# design.net
KiCad netlist of a schematic drawn in Altium Designer
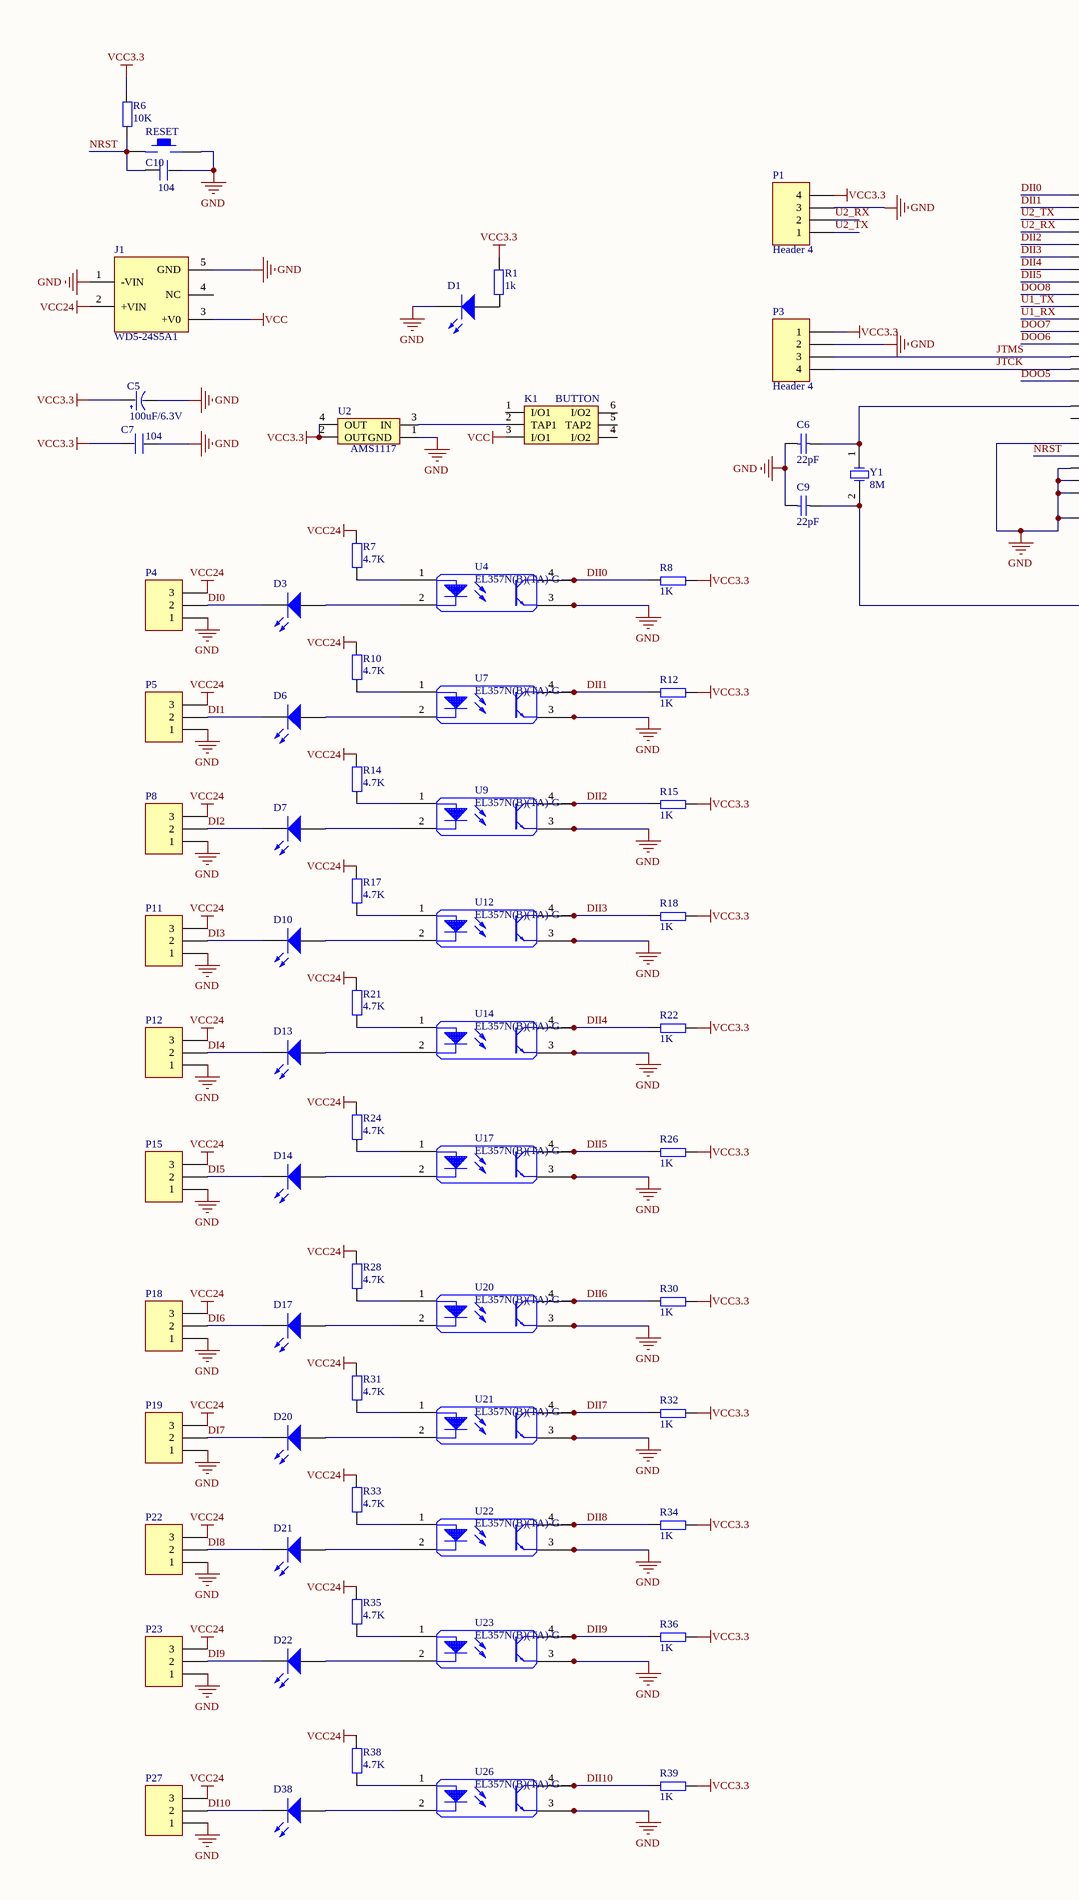
[diagram p0: 继电器板.SchDoc, left]
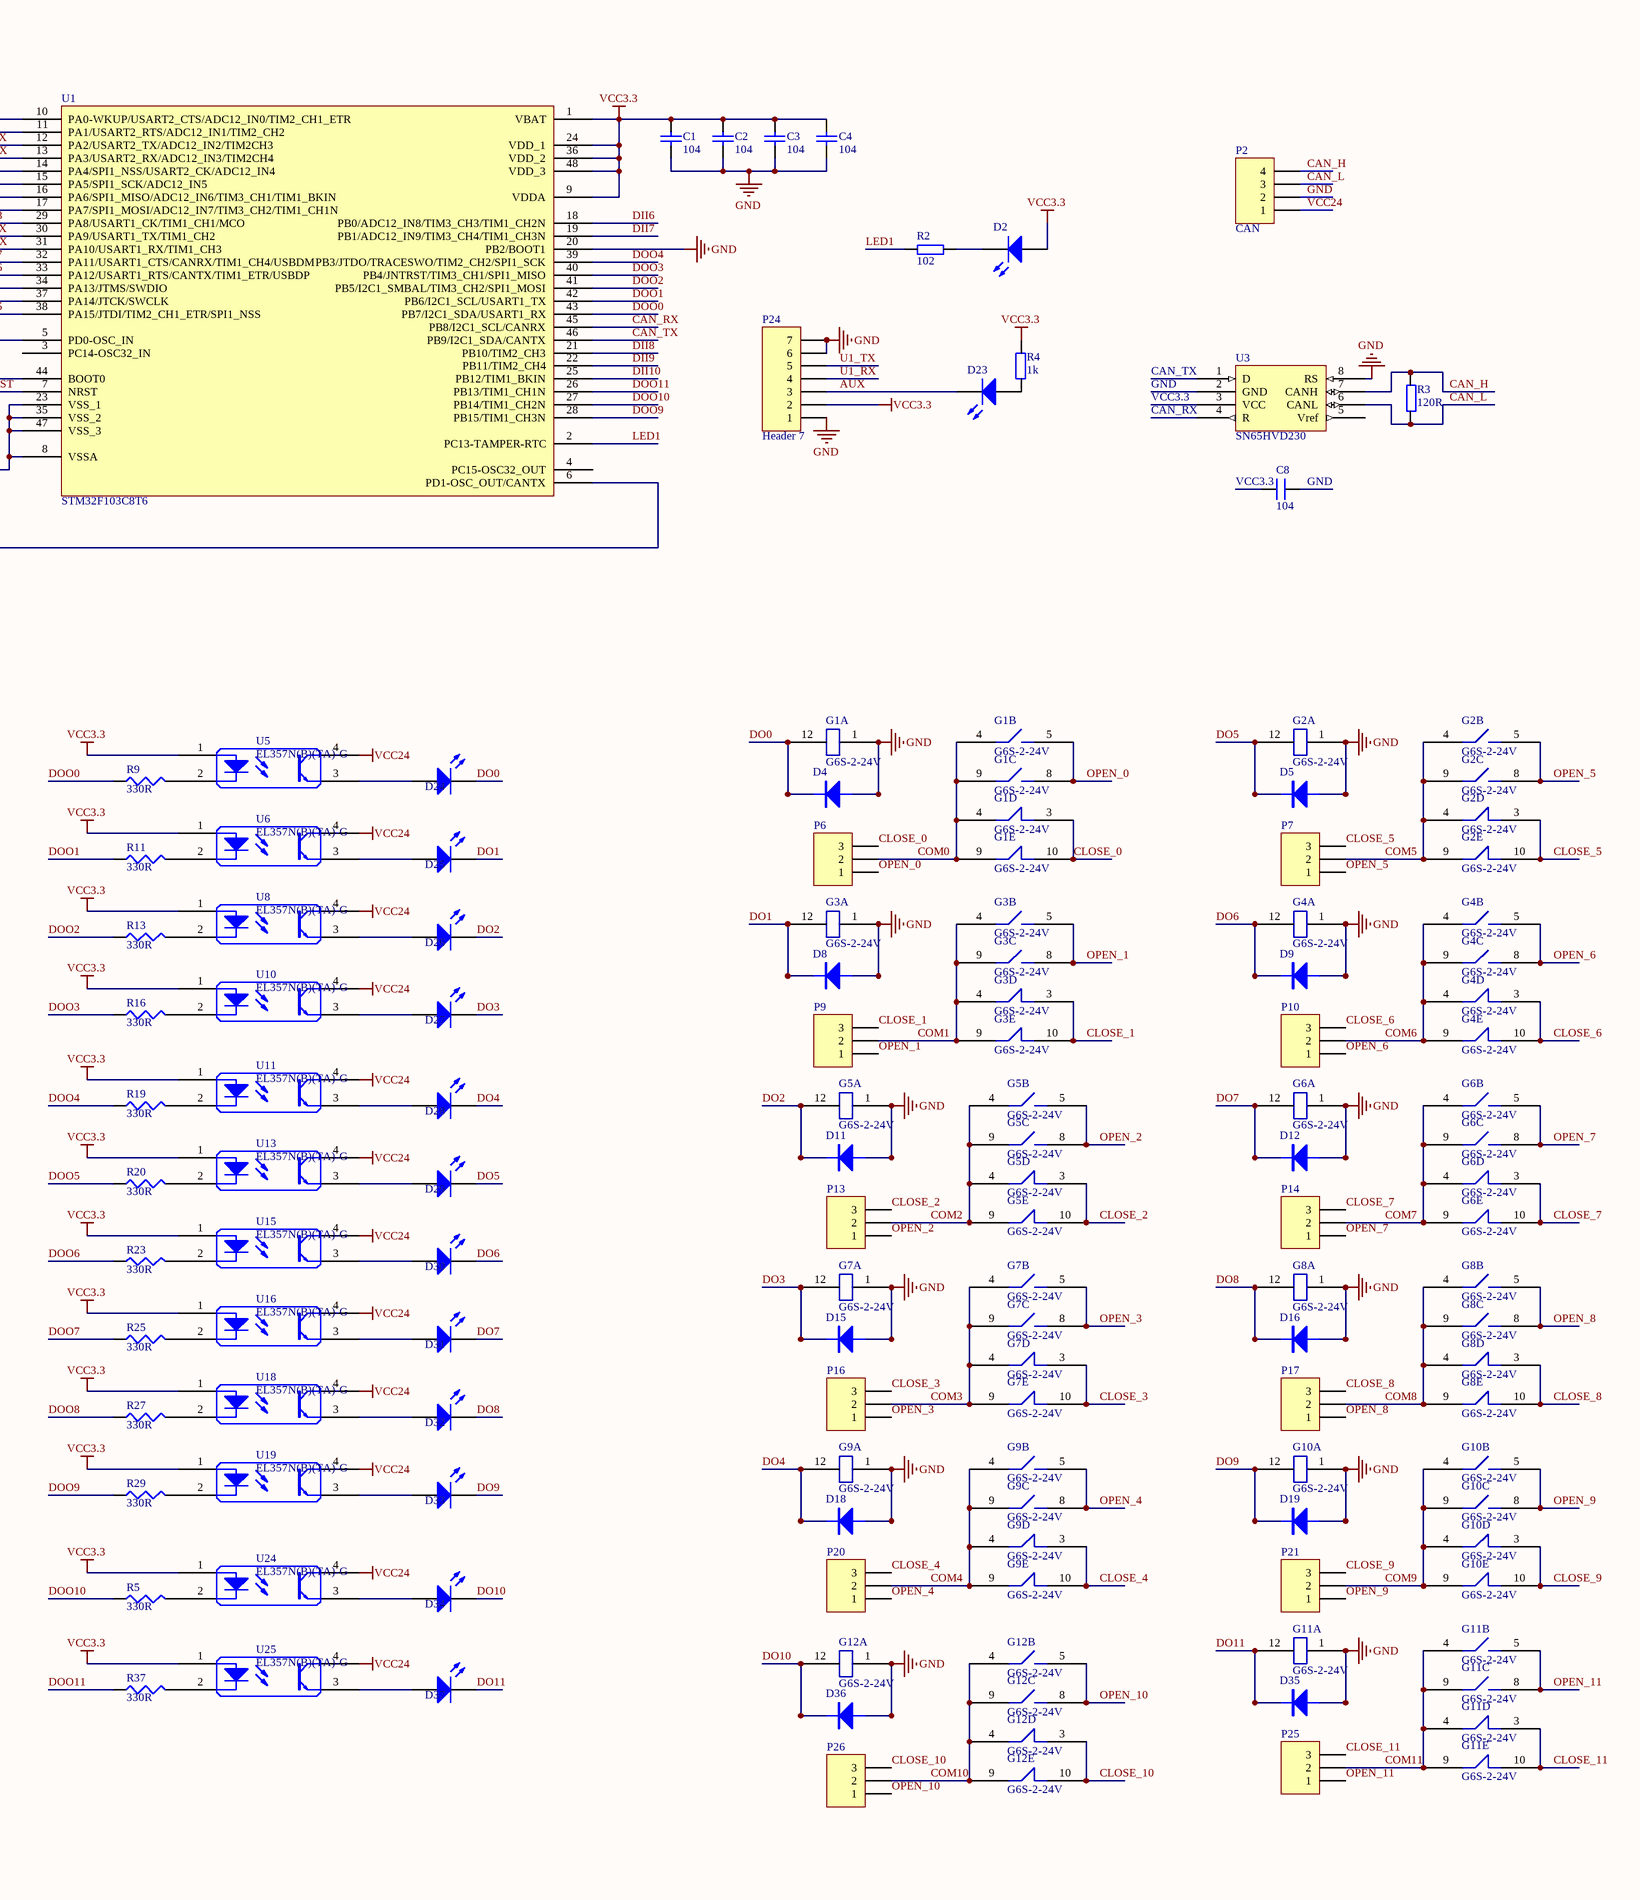
[diagram p1: 继电器板.SchDoc, right]

(export (version "E")
  (design (tool "Eeschema 10.0.6"))
  (components
    (comp (ref "C1")
      (value "104")
      (footprint "C0805")
      (description "Capacitor")
      (fields (field (name "PUBLISHER") "Altium Limited"))
      (libsource (lib "Miscellaneous Devices") (part "Cap"))
    )
    (comp (ref "C2")
      (value "104")
      (footprint "C0805")
      (description "Capacitor")
      (fields (field (name "PUBLISHER") "Altium Limited"))
      (libsource (lib "Miscellaneous Devices") (part "Cap"))
    )
    (comp (ref "C3")
      (value "104")
      (footprint "C0805")
      (description "Capacitor")
      (fields (field (name "PUBLISHER") "Altium Limited"))
      (libsource (lib "Miscellaneous Devices") (part "Cap"))
    )
    (comp (ref "C4")
      (value "104")
      (footprint "C0805")
      (description "Capacitor")
      (fields (field (name "PUBLISHER") "Altium Limited"))
      (libsource (lib "Miscellaneous Devices") (part "Cap"))
    )
    (comp (ref "C5") (value "100uF/6.3V") (footprint "3216") (libsource (lib "WarShip V3_SCH") (part "CAP")))
    (comp (ref "C6")
      (value "22pF")
      (footprint "C0805")
      (description "Capacitor")
      (fields (field (name "PUBLISHER") "Altium Limited"))
      (libsource (lib "Miscellaneous Devices") (part "Cap"))
    )
    (comp (ref "C7") (value "104") (footprint "C0805") (libsource (lib "WarShip V3_SCH") (part "C")))
    (comp (ref "C8") (value "104") (footprint "C0805") (libsource (lib "Explorer STM32F407封装库") (part "C_3")))
    (comp (ref "C9")
      (value "22pF")
      (footprint "C0805")
      (description "Capacitor")
      (fields (field (name "PUBLISHER") "Altium Limited"))
      (libsource (lib "Miscellaneous Devices") (part "Cap"))
    )
    (comp (ref "C10") (value "104") (footprint "C0805") (libsource (lib "Explorer STM32F407封装库") (part "C")))
    (comp (ref "D1")
      (value "LED0")
      (footprint "LC-0805_LED_S1")
      (description "Typical INFRARED GaAs LED")
      (fields (field (name "PUBLISHER") "Altium Limited"))
      (libsource (lib "继电器板_1") (part "LED0"))
    )
    (comp (ref "D2")
      (value "LED0")
      (footprint "LC-0805_LED_S1")
      (description "Typical INFRARED GaAs LED")
      (fields (field (name "PUBLISHER") "Altium Limited"))
      (libsource (lib "继电器板_1") (part "LED0"))
    )
    (comp (ref "D3")
      (value "LED0")
      (footprint "LC-0805_LED_S1")
      (description "Typical INFRARED GaAs LED")
      (fields (field (name "PUBLISHER") "Altium Limited"))
      (libsource (lib "继电器板_1") (part "LED0"))
    )
    (comp (ref "D4")
      (value "~")
      (footprint "LC-LL-34")
      (description "Diode")
      (libsource (lib "*") (part "DIODE"))
    )
    (comp (ref "D5")
      (value "~")
      (footprint "LC-LL-34")
      (description "Diode")
      (libsource (lib "*") (part "DIODE"))
    )
    (comp (ref "D6")
      (value "LED0")
      (footprint "LC-0805_LED_S1")
      (description "Typical INFRARED GaAs LED")
      (fields (field (name "PUBLISHER") "Altium Limited"))
      (libsource (lib "继电器板_1") (part "LED0"))
    )
    (comp (ref "D7")
      (value "LED0")
      (footprint "LC-0805_LED_S1")
      (description "Typical INFRARED GaAs LED")
      (fields (field (name "PUBLISHER") "Altium Limited"))
      (libsource (lib "继电器板_1") (part "LED0"))
    )
    (comp (ref "D8")
      (value "~")
      (footprint "LC-LL-34")
      (description "Diode")
      (libsource (lib "*") (part "DIODE"))
    )
    (comp (ref "D9")
      (value "~")
      (footprint "LC-LL-34")
      (description "Diode")
      (libsource (lib "*") (part "DIODE"))
    )
    (comp (ref "D10")
      (value "LED0")
      (footprint "LC-0805_LED_S1")
      (description "Typical INFRARED GaAs LED")
      (fields (field (name "PUBLISHER") "Altium Limited"))
      (libsource (lib "继电器板_1") (part "LED0"))
    )
    (comp (ref "D11")
      (value "~")
      (footprint "LC-LL-34")
      (description "Diode")
      (libsource (lib "*") (part "DIODE"))
    )
    (comp (ref "D12")
      (value "~")
      (footprint "LC-LL-34")
      (description "Diode")
      (libsource (lib "*") (part "DIODE"))
    )
    (comp (ref "D13")
      (value "LED0")
      (footprint "LC-0805_LED_S1")
      (description "Typical INFRARED GaAs LED")
      (fields (field (name "PUBLISHER") "Altium Limited"))
      (libsource (lib "继电器板_1") (part "LED0"))
    )
    (comp (ref "D14")
      (value "LED0")
      (footprint "LC-0805_LED_S1")
      (description "Typical INFRARED GaAs LED")
      (fields (field (name "PUBLISHER") "Altium Limited"))
      (libsource (lib "继电器板_1") (part "LED0"))
    )
    (comp (ref "D15")
      (value "~")
      (footprint "LC-LL-34")
      (description "Diode")
      (libsource (lib "*") (part "DIODE"))
    )
    (comp (ref "D16")
      (value "~")
      (footprint "LC-LL-34")
      (description "Diode")
      (libsource (lib "*") (part "DIODE"))
    )
    (comp (ref "D17")
      (value "LED0")
      (footprint "LC-0805_LED_S1")
      (description "Typical INFRARED GaAs LED")
      (fields (field (name "PUBLISHER") "Altium Limited"))
      (libsource (lib "继电器板_1") (part "LED0"))
    )
    (comp (ref "D18")
      (value "~")
      (footprint "LC-LL-34")
      (description "Diode")
      (libsource (lib "*") (part "DIODE"))
    )
    (comp (ref "D19")
      (value "~")
      (footprint "LC-LL-34")
      (description "Diode")
      (libsource (lib "*") (part "DIODE"))
    )
    (comp (ref "D20")
      (value "LED0")
      (footprint "LC-0805_LED_S1")
      (description "Typical INFRARED GaAs LED")
      (fields (field (name "PUBLISHER") "Altium Limited"))
      (libsource (lib "继电器板_1") (part "LED0"))
    )
    (comp (ref "D21")
      (value "LED0")
      (footprint "LC-0805_LED_S1")
      (description "Typical INFRARED GaAs LED")
      (fields (field (name "PUBLISHER") "Altium Limited"))
      (libsource (lib "继电器板_1") (part "LED0"))
    )
    (comp (ref "D22")
      (value "LED0")
      (footprint "LC-0805_LED_S1")
      (description "Typical INFRARED GaAs LED")
      (fields (field (name "PUBLISHER") "Altium Limited"))
      (libsource (lib "继电器板_1") (part "LED0"))
    )
    (comp (ref "D23")
      (value "LED0")
      (footprint "LC-0805_LED_S1")
      (description "Typical INFRARED GaAs LED")
      (fields (field (name "PUBLISHER") "Altium Limited"))
      (libsource (lib "继电器板_1") (part "LED0"))
    )
    (comp (ref "D24")
      (value "LED0")
      (footprint "LC-0805_LED_S1")
      (description "Typical INFRARED GaAs LED")
      (fields (field (name "PUBLISHER") "Altium Limited"))
      (libsource (lib "继电器板_1") (part "LED0"))
    )
    (comp (ref "D25")
      (value "LED0")
      (footprint "LC-0805_LED_S1")
      (description "Typical INFRARED GaAs LED")
      (fields (field (name "PUBLISHER") "Altium Limited"))
      (libsource (lib "继电器板_1") (part "LED0"))
    )
    (comp (ref "D26")
      (value "LED0")
      (footprint "LC-0805_LED_S1")
      (description "Typical INFRARED GaAs LED")
      (fields (field (name "PUBLISHER") "Altium Limited"))
      (libsource (lib "继电器板_1") (part "LED0"))
    )
    (comp (ref "D27")
      (value "LED0")
      (footprint "LC-0805_LED_S1")
      (description "Typical INFRARED GaAs LED")
      (fields (field (name "PUBLISHER") "Altium Limited"))
      (libsource (lib "继电器板_1") (part "LED0"))
    )
    (comp (ref "D28")
      (value "LED0")
      (footprint "LC-0805_LED_S1")
      (description "Typical INFRARED GaAs LED")
      (fields (field (name "PUBLISHER") "Altium Limited"))
      (libsource (lib "继电器板_1") (part "LED0"))
    )
    (comp (ref "D29")
      (value "LED0")
      (footprint "LC-0805_LED_S1")
      (description "Typical INFRARED GaAs LED")
      (fields (field (name "PUBLISHER") "Altium Limited"))
      (libsource (lib "继电器板_1") (part "LED0"))
    )
    (comp (ref "D30")
      (value "LED0")
      (footprint "LC-0805_LED_S1")
      (description "Typical INFRARED GaAs LED")
      (fields (field (name "PUBLISHER") "Altium Limited"))
      (libsource (lib "继电器板_1") (part "LED0"))
    )
    (comp (ref "D31")
      (value "LED0")
      (footprint "LC-0805_LED_S1")
      (description "Typical INFRARED GaAs LED")
      (fields (field (name "PUBLISHER") "Altium Limited"))
      (libsource (lib "继电器板_1") (part "LED0"))
    )
    (comp (ref "D32")
      (value "LED0")
      (footprint "LC-0805_LED_S1")
      (description "Typical INFRARED GaAs LED")
      (fields (field (name "PUBLISHER") "Altium Limited"))
      (libsource (lib "继电器板_1") (part "LED0"))
    )
    (comp (ref "D33")
      (value "LED0")
      (footprint "LC-0805_LED_S1")
      (description "Typical INFRARED GaAs LED")
      (fields (field (name "PUBLISHER") "Altium Limited"))
      (libsource (lib "继电器板_1") (part "LED0"))
    )
    (comp (ref "D34")
      (value "LED0")
      (footprint "LC-0805_LED_S1")
      (description "Typical INFRARED GaAs LED")
      (fields (field (name "PUBLISHER") "Altium Limited"))
      (libsource (lib "继电器板_1") (part "LED0"))
    )
    (comp (ref "D35")
      (value "~")
      (footprint "LC-LL-34")
      (description "Diode")
      (libsource (lib "*") (part "DIODE"))
    )
    (comp (ref "D36")
      (value "~")
      (footprint "LC-LL-34")
      (description "Diode")
      (libsource (lib "*") (part "DIODE"))
    )
    (comp (ref "D37")
      (value "LED0")
      (footprint "LC-0805_LED_S1")
      (description "Typical INFRARED GaAs LED")
      (fields (field (name "PUBLISHER") "Altium Limited"))
      (libsource (lib "继电器板_1") (part "LED0"))
    )
    (comp (ref "D38")
      (value "LED0")
      (footprint "LC-0805_LED_S1")
      (description "Typical INFRARED GaAs LED")
      (fields (field (name "PUBLISHER") "Altium Limited"))
      (libsource (lib "继电器板_1") (part "LED0"))
    )
    (comp (ref "G1")
      (value "G6S-2-24V")
      (footprint "G6S-2-24V")
      (description "G5SB-14-24VDC")
      (libsource (lib "altium-import") (part "root_0__继电器板.SchLib"))
    )
    (comp (ref "G2")
      (value "G6S-2-24V")
      (footprint "G6S-2-24V")
      (description "G5SB-14-24VDC")
      (libsource (lib "altium-import") (part "root_0__继电器板.SchLib"))
    )
    (comp (ref "G3")
      (value "G6S-2-24V")
      (footprint "G6S-2-24V")
      (description "G5SB-14-24VDC")
      (libsource (lib "altium-import") (part "root_2__继电器板.SchLib"))
    )
    (comp (ref "G4")
      (value "G6S-2-24V")
      (footprint "G6S-2-24V")
      (description "G5SB-14-24VDC")
      (libsource (lib "altium-import") (part "root_0__继电器板.SchLib"))
    )
    (comp (ref "G5")
      (value "G6S-2-24V")
      (footprint "G6S-2-24V")
      (description "G5SB-14-24VDC")
      (libsource (lib "altium-import") (part "root_2__继电器板.SchLib"))
    )
    (comp (ref "G6")
      (value "G6S-2-24V")
      (footprint "G6S-2-24V")
      (description "G5SB-14-24VDC")
      (libsource (lib "altium-import") (part "root_0__继电器板.SchLib"))
    )
    (comp (ref "G7")
      (value "G6S-2-24V")
      (footprint "G6S-2-24V")
      (description "G5SB-14-24VDC")
      (libsource (lib "altium-import") (part "root_0__继电器板.SchLib"))
    )
    (comp (ref "G8")
      (value "G6S-2-24V")
      (footprint "G6S-2-24V")
      (description "G5SB-14-24VDC")
      (libsource (lib "altium-import") (part "root_2__继电器板.SchLib"))
    )
    (comp (ref "G9")
      (value "G6S-2-24V")
      (footprint "G6S-2-24V")
      (description "G5SB-14-24VDC")
      (libsource (lib "altium-import") (part "root_0__继电器板.SchLib"))
    )
    (comp (ref "G10")
      (value "G6S-2-24V")
      (footprint "G6S-2-24V")
      (description "G5SB-14-24VDC")
      (libsource (lib "altium-import") (part "root_0__继电器板.SchLib"))
    )
    (comp (ref "G11")
      (value "G6S-2-24V")
      (footprint "G6S-2-24V")
      (description "G5SB-14-24VDC")
      (libsource (lib "altium-import") (part "root_0__继电器板.SchLib"))
    )
    (comp (ref "G12")
      (value "G6S-2-24V")
      (footprint "G6S-2-24V")
      (description "G5SB-14-24VDC")
      (libsource (lib "altium-import") (part "root_0__继电器板.SchLib"))
    )
    (comp (ref "J1")
      (value "WD5-24S5A1")
      (footprint "WD5-24S3V3")
      (libsource (lib "*") (part "WD5-24S3V3A1"))
    )
    (comp (ref "K1")
      (value "BUTTON")
      (footprint "BTN8.5*8.5")
      (libsource (lib "WarShip V3_SCH") (part "BUTTON"))
    )
    (comp (ref "P1")
      (value "Header 4")
      (footprint "HDR1X4")
      (description "Header, 4-Pin")
      (fields (field (name "PUBLISHER") "Altium Limited"))
      (libsource (lib "") (part "Header 4_1"))
    )
    (comp (ref "P2")
      (value "CAN")
      (footprint "DZ-4-3.5")
      (description "Header, 4-Pin")
      (fields (field (name "PUBLISHER") "Altium Limited"))
      (libsource (lib "") (part "Header 4_1"))
    )
    (comp (ref "P3")
      (value "Header 4")
      (footprint "IDE4")
      (description "Header, 4-Pin")
      (fields (field (name "PUBLISHER") "Altium Limited"))
      (libsource (lib "Miscellaneous Connectors") (part "Header 4"))
    )
    (comp (ref "P4")
      (value "~")
      (footprint "DZ-3-3.5")
      (description "Header, 3-Pin")
      (fields (field (name "PUBLISHER") "Altium Limited"))
      (libsource (lib "Miscellaneous Connectors") (part "Header 3"))
    )
    (comp (ref "P5")
      (value "~")
      (footprint "DZ-3-3.5")
      (description "Header, 3-Pin")
      (fields (field (name "PUBLISHER") "Altium Limited"))
      (libsource (lib "Miscellaneous Connectors") (part "Header 3"))
    )
    (comp (ref "P6")
      (value "~")
      (footprint "DZ-3-3.5")
      (description "Header, 3-Pin")
      (fields (field (name "PUBLISHER") "Altium Limited"))
      (libsource (lib "Miscellaneous Connectors") (part "Header 3"))
    )
    (comp (ref "P7")
      (value "~")
      (footprint "DZ-3-3.5")
      (description "Header, 3-Pin")
      (fields (field (name "PUBLISHER") "Altium Limited"))
      (libsource (lib "Miscellaneous Connectors") (part "Header 3"))
    )
    (comp (ref "P8")
      (value "~")
      (footprint "DZ-3-3.5")
      (description "Header, 3-Pin")
      (fields (field (name "PUBLISHER") "Altium Limited"))
      (libsource (lib "Miscellaneous Connectors") (part "Header 3"))
    )
    (comp (ref "P9")
      (value "~")
      (footprint "DZ-3-3.5")
      (description "Header, 3-Pin")
      (fields (field (name "PUBLISHER") "Altium Limited"))
      (libsource (lib "Miscellaneous Connectors") (part "Header 3"))
    )
    (comp (ref "P10")
      (value "~")
      (footprint "DZ-3-3.5")
      (description "Header, 3-Pin")
      (fields (field (name "PUBLISHER") "Altium Limited"))
      (libsource (lib "Miscellaneous Connectors") (part "Header 3"))
    )
    (comp (ref "P11")
      (value "~")
      (footprint "DZ-3-3.5")
      (description "Header, 3-Pin")
      (fields (field (name "PUBLISHER") "Altium Limited"))
      (libsource (lib "Miscellaneous Connectors") (part "Header 3"))
    )
    (comp (ref "P12")
      (value "~")
      (footprint "DZ-3-3.5")
      (description "Header, 3-Pin")
      (fields (field (name "PUBLISHER") "Altium Limited"))
      (libsource (lib "Miscellaneous Connectors") (part "Header 3"))
    )
    (comp (ref "P13")
      (value "~")
      (footprint "DZ-3-3.5")
      (description "Header, 3-Pin")
      (fields (field (name "PUBLISHER") "Altium Limited"))
      (libsource (lib "Miscellaneous Connectors") (part "Header 3"))
    )
    (comp (ref "P14")
      (value "~")
      (footprint "DZ-3-3.5")
      (description "Header, 3-Pin")
      (fields (field (name "PUBLISHER") "Altium Limited"))
      (libsource (lib "Miscellaneous Connectors") (part "Header 3"))
    )
    (comp (ref "P15")
      (value "~")
      (footprint "DZ-3-3.5")
      (description "Header, 3-Pin")
      (fields (field (name "PUBLISHER") "Altium Limited"))
      (libsource (lib "Miscellaneous Connectors") (part "Header 3"))
    )
    (comp (ref "P16")
      (value "~")
      (footprint "DZ-3-3.5")
      (description "Header, 3-Pin")
      (fields (field (name "PUBLISHER") "Altium Limited"))
      (libsource (lib "Miscellaneous Connectors") (part "Header 3"))
    )
    (comp (ref "P17")
      (value "~")
      (footprint "DZ-3-3.5")
      (description "Header, 3-Pin")
      (fields (field (name "PUBLISHER") "Altium Limited"))
      (libsource (lib "Miscellaneous Connectors") (part "Header 3"))
    )
    (comp (ref "P18")
      (value "~")
      (footprint "DZ-3-3.5")
      (description "Header, 3-Pin")
      (fields (field (name "PUBLISHER") "Altium Limited"))
      (libsource (lib "Miscellaneous Connectors") (part "Header 3"))
    )
    (comp (ref "P19")
      (value "~")
      (footprint "DZ-3-3.5")
      (description "Header, 3-Pin")
      (fields (field (name "PUBLISHER") "Altium Limited"))
      (libsource (lib "Miscellaneous Connectors") (part "Header 3"))
    )
    (comp (ref "P20")
      (value "~")
      (footprint "DZ-3-3.5")
      (description "Header, 3-Pin")
      (fields (field (name "PUBLISHER") "Altium Limited"))
      (libsource (lib "Miscellaneous Connectors") (part "Header 3"))
    )
    (comp (ref "P21")
      (value "~")
      (footprint "DZ-3-3.5")
      (description "Header, 3-Pin")
      (fields (field (name "PUBLISHER") "Altium Limited"))
      (libsource (lib "Miscellaneous Connectors") (part "Header 3"))
    )
    (comp (ref "P22")
      (value "~")
      (footprint "DZ-3-3.5")
      (description "Header, 3-Pin")
      (fields (field (name "PUBLISHER") "Altium Limited"))
      (libsource (lib "Miscellaneous Connectors") (part "Header 3"))
    )
    (comp (ref "P23")
      (value "~")
      (footprint "DZ-3-3.5")
      (description "Header, 3-Pin")
      (fields (field (name "PUBLISHER") "Altium Limited"))
      (libsource (lib "Miscellaneous Connectors") (part "Header 3"))
    )
    (comp (ref "P24")
      (value "Header 7")
      (footprint "AS50-T27")
      (description "Header, 7-Pin")
      (fields (field (name "PUBLISHER") "Altium Limited"))
      (libsource (lib "Miscellaneous Connectors") (part "Header 7"))
    )
    (comp (ref "P25")
      (value "~")
      (footprint "DZ-3-3.5")
      (description "Header, 3-Pin")
      (fields (field (name "PUBLISHER") "Altium Limited"))
      (libsource (lib "Miscellaneous Connectors") (part "Header 3"))
    )
    (comp (ref "P26")
      (value "~")
      (footprint "DZ-3-3.5")
      (description "Header, 3-Pin")
      (fields (field (name "PUBLISHER") "Altium Limited"))
      (libsource (lib "Miscellaneous Connectors") (part "Header 3"))
    )
    (comp (ref "P27")
      (value "~")
      (footprint "DZ-3-3.5")
      (description "Header, 3-Pin")
      (fields (field (name "PUBLISHER") "Altium Limited"))
      (libsource (lib "Miscellaneous Connectors") (part "Header 3"))
    )
    (comp (ref "R1") (value "1k") (footprint "0805") (libsource (lib "Explorer STM32F407封装库") (part "R_2")))
    (comp (ref "R2") (value "102") (footprint "0805") (libsource (lib "Explorer STM32F407封装库") (part "R_2")))
    (comp (ref "R3") (value "120R") (footprint "0805") (libsource (lib "Explorer STM32F407封装库") (part "R_2")))
    (comp (ref "R4") (value "1k") (footprint "0805") (libsource (lib "Explorer STM32F407封装库") (part "R_2")))
    (comp (ref "R5") (value "330R") (footprint "0805") (libsource (lib "*") (part "RES1")))
    (comp (ref "R6") (value "10K") (footprint "0805") (libsource (lib "Explorer STM32F407封装库") (part "R_2")))
    (comp (ref "R7") (value "4.7K") (footprint "0805") (libsource (lib "Explorer STM32F407封装库") (part "R_2")))
    (comp (ref "R8") (value "1K") (footprint "0805") (libsource (lib "Explorer STM32F407封装库") (part "R_2")))
    (comp (ref "R9") (value "330R") (footprint "0805") (libsource (lib "*") (part "RES1")))
    (comp (ref "R10")
      (value "4.7K")
      (footprint "0805")
      (libsource (lib "Explorer STM32F407封装库") (part "R_2"))
    )
    (comp (ref "R11") (value "330R") (footprint "0805") (libsource (lib "*") (part "RES1")))
    (comp (ref "R12") (value "1K") (footprint "0805") (libsource (lib "Explorer STM32F407封装库") (part "R_2")))
    (comp (ref "R13") (value "330R") (footprint "0805") (libsource (lib "*") (part "RES1")))
    (comp (ref "R14")
      (value "4.7K")
      (footprint "0805")
      (libsource (lib "Explorer STM32F407封装库") (part "R_2"))
    )
    (comp (ref "R15") (value "1K") (footprint "0805") (libsource (lib "Explorer STM32F407封装库") (part "R_2")))
    (comp (ref "R16") (value "330R") (footprint "0805") (libsource (lib "*") (part "RES1")))
    (comp (ref "R17")
      (value "4.7K")
      (footprint "0805")
      (libsource (lib "Explorer STM32F407封装库") (part "R_2"))
    )
    (comp (ref "R18") (value "1K") (footprint "0805") (libsource (lib "Explorer STM32F407封装库") (part "R_2")))
    (comp (ref "R19") (value "330R") (footprint "0805") (libsource (lib "*") (part "RES1")))
    (comp (ref "R20") (value "330R") (footprint "0805") (libsource (lib "*") (part "RES1")))
    (comp (ref "R21")
      (value "4.7K")
      (footprint "0805")
      (libsource (lib "Explorer STM32F407封装库") (part "R_2"))
    )
    (comp (ref "R22") (value "1K") (footprint "0805") (libsource (lib "Explorer STM32F407封装库") (part "R_2")))
    (comp (ref "R23") (value "330R") (footprint "0805") (libsource (lib "*") (part "RES1")))
    (comp (ref "R24")
      (value "4.7K")
      (footprint "0805")
      (libsource (lib "Explorer STM32F407封装库") (part "R_2"))
    )
    (comp (ref "R25") (value "330R") (footprint "0805") (libsource (lib "*") (part "RES1")))
    (comp (ref "R26") (value "1K") (footprint "0805") (libsource (lib "Explorer STM32F407封装库") (part "R_2")))
    (comp (ref "R27") (value "330R") (footprint "0805") (libsource (lib "*") (part "RES1")))
    (comp (ref "R28")
      (value "4.7K")
      (footprint "0805")
      (libsource (lib "Explorer STM32F407封装库") (part "R_2"))
    )
    (comp (ref "R29") (value "330R") (footprint "0805") (libsource (lib "*") (part "RES1")))
    (comp (ref "R30") (value "1K") (footprint "0805") (libsource (lib "Explorer STM32F407封装库") (part "R_2")))
    (comp (ref "R31")
      (value "4.7K")
      (footprint "0805")
      (libsource (lib "Explorer STM32F407封装库") (part "R_2"))
    )
    (comp (ref "R32") (value "1K") (footprint "0805") (libsource (lib "Explorer STM32F407封装库") (part "R_2")))
    (comp (ref "R33")
      (value "4.7K")
      (footprint "0805")
      (libsource (lib "Explorer STM32F407封装库") (part "R_2"))
    )
    (comp (ref "R34") (value "1K") (footprint "0805") (libsource (lib "Explorer STM32F407封装库") (part "R_2")))
    (comp (ref "R35")
      (value "4.7K")
      (footprint "0805")
      (libsource (lib "Explorer STM32F407封装库") (part "R_2"))
    )
    (comp (ref "R36") (value "1K") (footprint "0805") (libsource (lib "Explorer STM32F407封装库") (part "R_2")))
    (comp (ref "R37") (value "330R") (footprint "0805") (libsource (lib "*") (part "RES1")))
    (comp (ref "R38")
      (value "4.7K")
      (footprint "0805")
      (libsource (lib "Explorer STM32F407封装库") (part "R_2"))
    )
    (comp (ref "R39") (value "1K") (footprint "0805") (libsource (lib "Explorer STM32F407封装库") (part "R_2")))
    (comp (ref "RESET")
      (value "KEY_M")
      (footprint "SW_PB2_A1")
      (libsource (lib "Explorer STM32F407封装库") (part "KEY_M"))
    )
    (comp (ref "U1")
      (value "STM32F103C8T6")
      (footprint "LC-LQFP-48")
      (libsource (lib "Schlib1") (part "stm32f103v8t6"))
    )
    (comp (ref "U2")
      (value "AMS1117")
      (footprint "LC-SOT-223")
      (libsource (lib "WarShip V3_SCH") (part "AMS1117"))
    )
    (comp (ref "U3")
      (value "SN65HVD230")
      (footprint "LC-SOIC-8_150mil")
      (libsource (lib "Explorer STM32F407封装库") (part "SN65HVD230D"))
    )
    (comp (ref "U4")
      (value "EL357N(B)(TA)-G")
      (footprint "LC-SOP-4_P2.54")
      (libsource (lib "*") (part "2701"))
    )
    (comp (ref "U5")
      (value "EL357N(B)(TA)-G")
      (footprint "LC-SOP-4_P2.54")
      (libsource (lib "*") (part "2701"))
    )
    (comp (ref "U6")
      (value "EL357N(B)(TA)-G")
      (footprint "LC-SOP-4_P2.54")
      (libsource (lib "*") (part "2701"))
    )
    (comp (ref "U7")
      (value "EL357N(B)(TA)-G")
      (footprint "LC-SOP-4_P2.54")
      (libsource (lib "*") (part "2701"))
    )
    (comp (ref "U8")
      (value "EL357N(B)(TA)-G")
      (footprint "LC-SOP-4_P2.54")
      (libsource (lib "*") (part "2701"))
    )
    (comp (ref "U9")
      (value "EL357N(B)(TA)-G")
      (footprint "LC-SOP-4_P2.54")
      (libsource (lib "*") (part "2701"))
    )
    (comp (ref "U10")
      (value "EL357N(B)(TA)-G")
      (footprint "LC-SOP-4_P2.54")
      (libsource (lib "*") (part "2701"))
    )
    (comp (ref "U11")
      (value "EL357N(B)(TA)-G")
      (footprint "LC-SOP-4_P2.54")
      (libsource (lib "*") (part "2701"))
    )
    (comp (ref "U12")
      (value "EL357N(B)(TA)-G")
      (footprint "LC-SOP-4_P2.54")
      (libsource (lib "*") (part "2701"))
    )
    (comp (ref "U13")
      (value "EL357N(B)(TA)-G")
      (footprint "LC-SOP-4_P2.54")
      (libsource (lib "*") (part "2701"))
    )
    (comp (ref "U14")
      (value "EL357N(B)(TA)-G")
      (footprint "LC-SOP-4_P2.54")
      (libsource (lib "*") (part "2701"))
    )
    (comp (ref "U15")
      (value "EL357N(B)(TA)-G")
      (footprint "LC-SOP-4_P2.54")
      (libsource (lib "*") (part "2701"))
    )
    (comp (ref "U16")
      (value "EL357N(B)(TA)-G")
      (footprint "LC-SOP-4_P2.54")
      (libsource (lib "*") (part "2701"))
    )
    (comp (ref "U17")
      (value "EL357N(B)(TA)-G")
      (footprint "LC-SOP-4_P2.54")
      (libsource (lib "*") (part "2701"))
    )
    (comp (ref "U18")
      (value "EL357N(B)(TA)-G")
      (footprint "LC-SOP-4_P2.54")
      (libsource (lib "*") (part "2701"))
    )
    (comp (ref "U19")
      (value "EL357N(B)(TA)-G")
      (footprint "LC-SOP-4_P2.54")
      (libsource (lib "*") (part "2701"))
    )
    (comp (ref "U20")
      (value "EL357N(B)(TA)-G")
      (footprint "LC-SOP-4_P2.54")
      (libsource (lib "*") (part "2701"))
    )
    (comp (ref "U21")
      (value "EL357N(B)(TA)-G")
      (footprint "LC-SOP-4_P2.54")
      (libsource (lib "*") (part "2701"))
    )
    (comp (ref "U22")
      (value "EL357N(B)(TA)-G")
      (footprint "LC-SOP-4_P2.54")
      (libsource (lib "*") (part "2701"))
    )
    (comp (ref "U23")
      (value "EL357N(B)(TA)-G")
      (footprint "LC-SOP-4_P2.54")
      (libsource (lib "*") (part "2701"))
    )
    (comp (ref "U24")
      (value "EL357N(B)(TA)-G")
      (footprint "LC-SOP-4_P2.54")
      (libsource (lib "*") (part "2701"))
    )
    (comp (ref "U25")
      (value "EL357N(B)(TA)-G")
      (footprint "LC-SOP-4_P2.54")
      (libsource (lib "*") (part "2701"))
    )
    (comp (ref "U26")
      (value "EL357N(B)(TA)-G")
      (footprint "LC-SOP-4_P2.54")
      (libsource (lib "*") (part "2701"))
    )
    (comp (ref "Y1")
      (value "8M")
      (footprint "XTAL_US")
      (description "Crystal Oscillator")
      (fields (field (name "PUBLISHER") "Altium Limited"))
      (libsource (lib "Miscellaneous Devices") (part "XTAL"))
    )
  )
  (nets
    (net (code "1") (name "/AUX") (class "Default")
      (node (ref "D23") (pin "K") (pinfunction "K_K") (pintype "passive"))
      (node (ref "P24") (pin "3") (pinfunction "3_3") (pintype "passive"))
    )
    (net (code "2") (name "/CAN_H") (class "Default")
      (node (ref "P2") (pin "4") (pinfunction "4_4") (pintype "passive"))
      (node (ref "R3") (pin "2") (pintype "passive"))
      (node (ref "U3") (pin "7") (pinfunction "CANH_7") (pintype "bidirectional"))
    )
    (net (code "3") (name "/CAN_L") (class "Default")
      (node (ref "P2") (pin "3") (pinfunction "3_3") (pintype "passive"))
      (node (ref "R3") (pin "1") (pintype "passive"))
      (node (ref "U3") (pin "6") (pinfunction "CANL_6") (pintype "bidirectional"))
    )
    (net (code "4") (name "/CAN_RX") (class "Default")
      (node (ref "U1") (pin "45") (pinfunction "PB8/I2C1_SCL/CANRX_45") (pintype "passive"))
      (node (ref "U3") (pin "4") (pinfunction "R_4") (pintype "output"))
    )
    (net (code "5") (name "/CAN_TX") (class "Default")
      (node (ref "U1") (pin "46") (pinfunction "PB9/I2C1_SDA/CANTX_46") (pintype "passive"))
      (node (ref "U3") (pin "1") (pinfunction "D_1") (pintype "input"))
    )
    (net (code "6") (name "/CLOSE_0") (class "Default")
      (node (ref "G1") (pin "10") (pinfunction "14_10") (pintype "passive"))
      (node (ref "G1") (pin "3") (pinfunction "14_3") (pintype "passive"))
      (node (ref "P6") (pin "3") (pinfunction "3_3") (pintype "passive"))
    )
    (net (code "7") (name "/CLOSE_1") (class "Default")
      (node (ref "G3") (pin "10") (pinfunction "14_10") (pintype "passive"))
      (node (ref "G3") (pin "3") (pinfunction "14_3") (pintype "passive"))
      (node (ref "P9") (pin "3") (pinfunction "3_3") (pintype "passive"))
    )
    (net (code "8") (name "/CLOSE_2") (class "Default")
      (node (ref "G5") (pin "10") (pinfunction "14_10") (pintype "passive"))
      (node (ref "G5") (pin "3") (pinfunction "14_3") (pintype "passive"))
      (node (ref "P13") (pin "3") (pinfunction "3_3") (pintype "passive"))
    )
    (net (code "9") (name "/CLOSE_3") (class "Default")
      (node (ref "G7") (pin "10") (pinfunction "14_10") (pintype "passive"))
      (node (ref "G7") (pin "3") (pinfunction "14_3") (pintype "passive"))
      (node (ref "P16") (pin "3") (pinfunction "3_3") (pintype "passive"))
    )
    (net (code "10") (name "/CLOSE_4") (class "Default")
      (node (ref "G9") (pin "10") (pinfunction "14_10") (pintype "passive"))
      (node (ref "G9") (pin "3") (pinfunction "14_3") (pintype "passive"))
      (node (ref "P20") (pin "3") (pinfunction "3_3") (pintype "passive"))
    )
    (net (code "11") (name "/CLOSE_5") (class "Default")
      (node (ref "G2") (pin "10") (pinfunction "14_10") (pintype "passive"))
      (node (ref "G2") (pin "3") (pinfunction "14_3") (pintype "passive"))
      (node (ref "P7") (pin "3") (pinfunction "3_3") (pintype "passive"))
    )
    (net (code "12") (name "/CLOSE_6") (class "Default")
      (node (ref "G4") (pin "10") (pinfunction "14_10") (pintype "passive"))
      (node (ref "G4") (pin "3") (pinfunction "14_3") (pintype "passive"))
      (node (ref "P10") (pin "3") (pinfunction "3_3") (pintype "passive"))
    )
    (net (code "13") (name "/CLOSE_7") (class "Default")
      (node (ref "G6") (pin "10") (pinfunction "14_10") (pintype "passive"))
      (node (ref "G6") (pin "3") (pinfunction "14_3") (pintype "passive"))
      (node (ref "P14") (pin "3") (pinfunction "3_3") (pintype "passive"))
    )
    (net (code "14") (name "/CLOSE_8") (class "Default")
      (node (ref "G8") (pin "10") (pinfunction "14_10") (pintype "passive"))
      (node (ref "G8") (pin "3") (pinfunction "14_3") (pintype "passive"))
      (node (ref "P17") (pin "3") (pinfunction "3_3") (pintype "passive"))
    )
    (net (code "15") (name "/CLOSE_9") (class "Default")
      (node (ref "G10") (pin "10") (pinfunction "14_10") (pintype "passive"))
      (node (ref "G10") (pin "3") (pinfunction "14_3") (pintype "passive"))
      (node (ref "P21") (pin "3") (pinfunction "3_3") (pintype "passive"))
    )
    (net (code "16") (name "/CLOSE_10") (class "Default")
      (node (ref "G12") (pin "10") (pinfunction "14_10") (pintype "passive"))
      (node (ref "G12") (pin "3") (pinfunction "14_3") (pintype "passive"))
      (node (ref "P26") (pin "3") (pinfunction "3_3") (pintype "passive"))
    )
    (net (code "17") (name "/CLOSE_11") (class "Default")
      (node (ref "G11") (pin "10") (pinfunction "14_10") (pintype "passive"))
      (node (ref "G11") (pin "3") (pinfunction "14_3") (pintype "passive"))
      (node (ref "P25") (pin "3") (pinfunction "3_3") (pintype "passive"))
    )
    (net (code "18") (name "/COM0") (class "Default")
      (node (ref "G1") (pin "4") (pinfunction "13_4") (pintype "passive"))
      (node (ref "G1") (pin "9") (pinfunction "13_9") (pintype "passive"))
      (node (ref "P6") (pin "2") (pinfunction "2_2") (pintype "passive"))
    )
    (net (code "19") (name "/COM1") (class "Default")
      (node (ref "G3") (pin "4") (pinfunction "13_4") (pintype "passive"))
      (node (ref "G3") (pin "9") (pinfunction "13_9") (pintype "passive"))
      (node (ref "P9") (pin "2") (pinfunction "2_2") (pintype "passive"))
    )
    (net (code "20") (name "/COM2") (class "Default")
      (node (ref "G5") (pin "4") (pinfunction "13_4") (pintype "passive"))
      (node (ref "G5") (pin "9") (pinfunction "13_9") (pintype "passive"))
      (node (ref "P13") (pin "2") (pinfunction "2_2") (pintype "passive"))
    )
    (net (code "21") (name "/COM3") (class "Default")
      (node (ref "G7") (pin "4") (pinfunction "13_4") (pintype "passive"))
      (node (ref "G7") (pin "9") (pinfunction "13_9") (pintype "passive"))
      (node (ref "P16") (pin "2") (pinfunction "2_2") (pintype "passive"))
    )
    (net (code "22") (name "/COM4") (class "Default")
      (node (ref "G9") (pin "4") (pinfunction "13_4") (pintype "passive"))
      (node (ref "G9") (pin "9") (pinfunction "13_9") (pintype "passive"))
      (node (ref "P20") (pin "2") (pinfunction "2_2") (pintype "passive"))
    )
    (net (code "23") (name "/COM5") (class "Default")
      (node (ref "G2") (pin "4") (pinfunction "13_4") (pintype "passive"))
      (node (ref "G2") (pin "9") (pinfunction "13_9") (pintype "passive"))
      (node (ref "P7") (pin "2") (pinfunction "2_2") (pintype "passive"))
    )
    (net (code "24") (name "/COM6") (class "Default")
      (node (ref "G4") (pin "4") (pinfunction "13_4") (pintype "passive"))
      (node (ref "G4") (pin "9") (pinfunction "13_9") (pintype "passive"))
      (node (ref "P10") (pin "2") (pinfunction "2_2") (pintype "passive"))
    )
    (net (code "25") (name "/COM7") (class "Default")
      (node (ref "G6") (pin "4") (pinfunction "13_4") (pintype "passive"))
      (node (ref "G6") (pin "9") (pinfunction "13_9") (pintype "passive"))
      (node (ref "P14") (pin "2") (pinfunction "2_2") (pintype "passive"))
    )
    (net (code "26") (name "/COM8") (class "Default")
      (node (ref "G8") (pin "4") (pinfunction "13_4") (pintype "passive"))
      (node (ref "G8") (pin "9") (pinfunction "13_9") (pintype "passive"))
      (node (ref "P17") (pin "2") (pinfunction "2_2") (pintype "passive"))
    )
    (net (code "27") (name "/COM9") (class "Default")
      (node (ref "G10") (pin "4") (pinfunction "13_4") (pintype "passive"))
      (node (ref "G10") (pin "9") (pinfunction "13_9") (pintype "passive"))
      (node (ref "P21") (pin "2") (pinfunction "2_2") (pintype "passive"))
    )
    (net (code "28") (name "/COM10") (class "Default")
      (node (ref "G12") (pin "4") (pinfunction "13_4") (pintype "passive"))
      (node (ref "G12") (pin "9") (pinfunction "13_9") (pintype "passive"))
      (node (ref "P26") (pin "2") (pinfunction "2_2") (pintype "passive"))
    )
    (net (code "29") (name "/COM11") (class "Default")
      (node (ref "G11") (pin "4") (pinfunction "13_4") (pintype "passive"))
      (node (ref "G11") (pin "9") (pinfunction "13_9") (pintype "passive"))
      (node (ref "P25") (pin "2") (pinfunction "2_2") (pintype "passive"))
    )
    (net (code "30") (name "/DI0") (class "Default")
      (node (ref "D3") (pin "K") (pinfunction "K_K") (pintype "passive"))
      (node (ref "P4") (pin "2") (pinfunction "2_2") (pintype "passive"))
    )
    (net (code "31") (name "/DI1") (class "Default")
      (node (ref "D6") (pin "K") (pinfunction "K_K") (pintype "passive"))
      (node (ref "P5") (pin "2") (pinfunction "2_2") (pintype "passive"))
    )
    (net (code "32") (name "/DI2") (class "Default")
      (node (ref "D7") (pin "K") (pinfunction "K_K") (pintype "passive"))
      (node (ref "P8") (pin "2") (pinfunction "2_2") (pintype "passive"))
    )
    (net (code "33") (name "/DI3") (class "Default")
      (node (ref "D10") (pin "K") (pinfunction "K_K") (pintype "passive"))
      (node (ref "P11") (pin "2") (pinfunction "2_2") (pintype "passive"))
    )
    (net (code "34") (name "/DI4") (class "Default")
      (node (ref "D13") (pin "K") (pinfunction "K_K") (pintype "passive"))
      (node (ref "P12") (pin "2") (pinfunction "2_2") (pintype "passive"))
    )
    (net (code "35") (name "/DI5") (class "Default")
      (node (ref "D14") (pin "K") (pinfunction "K_K") (pintype "passive"))
      (node (ref "P15") (pin "2") (pinfunction "2_2") (pintype "passive"))
    )
    (net (code "36") (name "/DI6") (class "Default")
      (node (ref "D17") (pin "K") (pinfunction "K_K") (pintype "passive"))
      (node (ref "P18") (pin "2") (pinfunction "2_2") (pintype "passive"))
    )
    (net (code "37") (name "/DI7") (class "Default")
      (node (ref "D20") (pin "K") (pinfunction "K_K") (pintype "passive"))
      (node (ref "P19") (pin "2") (pinfunction "2_2") (pintype "passive"))
    )
    (net (code "38") (name "/DI8") (class "Default")
      (node (ref "D21") (pin "K") (pinfunction "K_K") (pintype "passive"))
      (node (ref "P22") (pin "2") (pinfunction "2_2") (pintype "passive"))
    )
    (net (code "39") (name "/DI9") (class "Default")
      (node (ref "D22") (pin "K") (pinfunction "K_K") (pintype "passive"))
      (node (ref "P23") (pin "2") (pinfunction "2_2") (pintype "passive"))
    )
    (net (code "40") (name "/DI10") (class "Default")
      (node (ref "D38") (pin "K") (pinfunction "K_K") (pintype "passive"))
      (node (ref "P27") (pin "2") (pinfunction "2_2") (pintype "passive"))
    )
    (net (code "41") (name "/DII0") (class "Default")
      (node (ref "R8") (pin "1") (pintype "passive"))
      (node (ref "U1") (pin "10") (pinfunction "PA0-WKUP/USART2_CTS/ADC12_IN0/TIM2_CH1_ETR_10") (pintype "passive"))
      (node (ref "U4") (pin "4") (pintype "passive"))
    )
    (net (code "42") (name "/DII1") (class "Default")
      (node (ref "R12") (pin "1") (pintype "passive"))
      (node (ref "U1") (pin "11") (pinfunction "PA1/USART2_RTS/ADC12_IN1/TIM2_CH2_11") (pintype "passive"))
      (node (ref "U7") (pin "4") (pintype "passive"))
    )
    (net (code "43") (name "/DII2") (class "Default")
      (node (ref "R15") (pin "1") (pintype "passive"))
      (node (ref "U1") (pin "14") (pinfunction "PA4/SPI1_NSS/USART2_CK/ADC12_IN4_14") (pintype "passive"))
      (node (ref "U9") (pin "4") (pintype "passive"))
    )
    (net (code "44") (name "/DII3") (class "Default")
      (node (ref "R18") (pin "1") (pintype "passive"))
      (node (ref "U1") (pin "15") (pinfunction "PA5/SPI1_SCK/ADC12_IN5_15") (pintype "passive"))
      (node (ref "U12") (pin "4") (pintype "passive"))
    )
    (net (code "45") (name "/DII4") (class "Default")
      (node (ref "R22") (pin "1") (pintype "passive"))
      (node (ref "U1") (pin "16") (pinfunction "PA6/SPI1_MISO/ADC12_IN6/TIM3_CH1/TIM1_BKIN_16") (pintype "passive"))
      (node (ref "U14") (pin "4") (pintype "passive"))
    )
    (net (code "46") (name "/DII5") (class "Default")
      (node (ref "R26") (pin "1") (pintype "passive"))
      (node (ref "U1") (pin "17") (pinfunction "PA7/SPI1_MOSI/ADC12_IN7/TIM3_CH2/TIM1_CH1N_17") (pintype "passive"))
      (node (ref "U17") (pin "4") (pintype "passive"))
    )
    (net (code "47") (name "/DII6") (class "Default")
      (node (ref "R30") (pin "1") (pintype "passive"))
      (node (ref "U1") (pin "18") (pinfunction "PB0/ADC12_IN8/TIM3_CH3/TIM1_CH2N_18") (pintype "passive"))
      (node (ref "U20") (pin "4") (pintype "passive"))
    )
    (net (code "48") (name "/DII7") (class "Default")
      (node (ref "R32") (pin "1") (pintype "passive"))
      (node (ref "U1") (pin "19") (pinfunction "PB1/ADC12_IN9/TIM3_CH4/TIM1_CH3N_19") (pintype "passive"))
      (node (ref "U21") (pin "4") (pintype "passive"))
    )
    (net (code "49") (name "/DII8") (class "Default")
      (node (ref "R34") (pin "1") (pintype "passive"))
      (node (ref "U1") (pin "21") (pinfunction "PB10/TIM2_CH3_21") (pintype "passive"))
      (node (ref "U22") (pin "4") (pintype "passive"))
    )
    (net (code "50") (name "/DII9") (class "Default")
      (node (ref "R36") (pin "1") (pintype "passive"))
      (node (ref "U1") (pin "22") (pinfunction "PB11/TIM2_CH4_22") (pintype "passive"))
      (node (ref "U23") (pin "4") (pintype "passive"))
    )
    (net (code "51") (name "/DII10") (class "Default")
      (node (ref "R39") (pin "1") (pintype "passive"))
      (node (ref "U1") (pin "25") (pinfunction "PB12/TIM1_BKIN_25") (pintype "passive"))
      (node (ref "U26") (pin "4") (pintype "passive"))
    )
    (net (code "52") (name "/DO0") (class "Default")
      (node (ref "D24") (pin "K") (pinfunction "K_K") (pintype "passive"))
      (node (ref "D4") (pin "2") (pinfunction "K_2") (pintype "passive"))
      (node (ref "G1") (pin "12") (pinfunction "2_12") (pintype "passive"))
    )
    (net (code "53") (name "/DO1") (class "Default")
      (node (ref "D25") (pin "K") (pinfunction "K_K") (pintype "passive"))
      (node (ref "D8") (pin "2") (pinfunction "K_2") (pintype "passive"))
      (node (ref "G3") (pin "12") (pinfunction "2_12") (pintype "passive"))
    )
    (net (code "54") (name "/DO2") (class "Default")
      (node (ref "D11") (pin "2") (pinfunction "K_2") (pintype "passive"))
      (node (ref "D26") (pin "K") (pinfunction "K_K") (pintype "passive"))
      (node (ref "G5") (pin "12") (pinfunction "2_12") (pintype "passive"))
    )
    (net (code "55") (name "/DO3") (class "Default")
      (node (ref "D15") (pin "2") (pinfunction "K_2") (pintype "passive"))
      (node (ref "D27") (pin "K") (pinfunction "K_K") (pintype "passive"))
      (node (ref "G7") (pin "12") (pinfunction "2_12") (pintype "passive"))
    )
    (net (code "56") (name "/DO4") (class "Default")
      (node (ref "D18") (pin "2") (pinfunction "K_2") (pintype "passive"))
      (node (ref "D28") (pin "K") (pinfunction "K_K") (pintype "passive"))
      (node (ref "G9") (pin "12") (pinfunction "2_12") (pintype "passive"))
    )
    (net (code "57") (name "/DO5") (class "Default")
      (node (ref "D29") (pin "K") (pinfunction "K_K") (pintype "passive"))
      (node (ref "D5") (pin "2") (pinfunction "K_2") (pintype "passive"))
      (node (ref "G2") (pin "12") (pinfunction "2_12") (pintype "passive"))
    )
    (net (code "58") (name "/DO6") (class "Default")
      (node (ref "D30") (pin "K") (pinfunction "K_K") (pintype "passive"))
      (node (ref "D9") (pin "2") (pinfunction "K_2") (pintype "passive"))
      (node (ref "G4") (pin "12") (pinfunction "2_12") (pintype "passive"))
    )
    (net (code "59") (name "/DO7") (class "Default")
      (node (ref "D12") (pin "2") (pinfunction "K_2") (pintype "passive"))
      (node (ref "D31") (pin "K") (pinfunction "K_K") (pintype "passive"))
      (node (ref "G6") (pin "12") (pinfunction "2_12") (pintype "passive"))
    )
    (net (code "60") (name "/DO8") (class "Default")
      (node (ref "D16") (pin "2") (pinfunction "K_2") (pintype "passive"))
      (node (ref "D32") (pin "K") (pinfunction "K_K") (pintype "passive"))
      (node (ref "G8") (pin "12") (pinfunction "2_12") (pintype "passive"))
    )
    (net (code "61") (name "/DO9") (class "Default")
      (node (ref "D19") (pin "2") (pinfunction "K_2") (pintype "passive"))
      (node (ref "D33") (pin "K") (pinfunction "K_K") (pintype "passive"))
      (node (ref "G10") (pin "12") (pinfunction "2_12") (pintype "passive"))
    )
    (net (code "62") (name "/DO10") (class "Default")
      (node (ref "D34") (pin "K") (pinfunction "K_K") (pintype "passive"))
      (node (ref "D36") (pin "2") (pinfunction "K_2") (pintype "passive"))
      (node (ref "G12") (pin "12") (pinfunction "2_12") (pintype "passive"))
    )
    (net (code "63") (name "/DO11") (class "Default")
      (node (ref "D35") (pin "2") (pinfunction "K_2") (pintype "passive"))
      (node (ref "D37") (pin "K") (pinfunction "K_K") (pintype "passive"))
      (node (ref "G11") (pin "12") (pinfunction "2_12") (pintype "passive"))
    )
    (net (code "64") (name "/DOO0") (class "Default")
      (node (ref "R9") (pin "1") (pintype "passive"))
      (node (ref "U1") (pin "43") (pinfunction "PB7/I2C1_SDA/USART1_RX_43") (pintype "passive"))
    )
    (net (code "65") (name "/DOO1") (class "Default")
      (node (ref "R11") (pin "1") (pintype "passive"))
      (node (ref "U1") (pin "42") (pinfunction "PB6/I2C1_SCL/USART1_TX_42") (pintype "passive"))
    )
    (net (code "66") (name "/DOO2") (class "Default")
      (node (ref "R13") (pin "1") (pintype "passive"))
      (node (ref "U1") (pin "41") (pinfunction "PB5/I2C1_SMBAL/TIM3_CH2/SPI1_MOSI_41") (pintype "passive"))
    )
    (net (code "67") (name "/DOO3") (class "Default")
      (node (ref "R16") (pin "1") (pintype "passive"))
      (node (ref "U1") (pin "40") (pinfunction "PB4/JNTRST/TIM3_CH1/SPI1_MISO_40") (pintype "passive"))
    )
    (net (code "68") (name "/DOO4") (class "Default")
      (node (ref "R19") (pin "1") (pintype "passive"))
      (node (ref "U1") (pin "39") (pinfunction "PB3/JTDO/TRACESWO/TIM2_CH2/SPI1_SCK_39") (pintype "passive"))
    )
    (net (code "69") (name "/DOO5") (class "Default")
      (node (ref "R20") (pin "1") (pintype "passive"))
      (node (ref "U1") (pin "38") (pinfunction "PA15/JTDI/TIM2_CH1_ETR/SPI1_NSS_38") (pintype "passive"))
    )
    (net (code "70") (name "/DOO6") (class "Default")
      (node (ref "R23") (pin "1") (pintype "passive"))
      (node (ref "U1") (pin "33") (pinfunction "PA12/USART1_RTS/CANTX/TIM1_ETR/USBDP_33") (pintype "passive"))
    )
    (net (code "71") (name "/DOO7") (class "Default")
      (node (ref "R25") (pin "1") (pintype "passive"))
      (node (ref "U1") (pin "32") (pinfunction "PA11/USART1_CTS/CANRX/TIM1_CH4/USBDM_32") (pintype "passive"))
    )
    (net (code "72") (name "/DOO8") (class "Default")
      (node (ref "R27") (pin "1") (pintype "passive"))
      (node (ref "U1") (pin "29") (pinfunction "PA8/USART1_CK/TIM1_CH1/MCO_29") (pintype "passive"))
    )
    (net (code "73") (name "/DOO9") (class "Default")
      (node (ref "R29") (pin "1") (pintype "passive"))
      (node (ref "U1") (pin "28") (pinfunction "PB15/TIM1_CH3N_28") (pintype "passive"))
    )
    (net (code "74") (name "/DOO10") (class "Default")
      (node (ref "R5") (pin "1") (pintype "passive"))
      (node (ref "U1") (pin "27") (pinfunction "PB14/TIM1_CH2N_27") (pintype "passive"))
    )
    (net (code "75") (name "/DOO11") (class "Default")
      (node (ref "R37") (pin "1") (pintype "passive"))
      (node (ref "U1") (pin "26") (pinfunction "PB13/TIM1_CH1N_26") (pintype "passive"))
    )
    (net (code "76") (name "/JTCK") (class "Default")
      (node (ref "P3") (pin "4") (pinfunction "4_4") (pintype "passive"))
      (node (ref "U1") (pin "37") (pinfunction "PA14/JTCK/SWCLK_37") (pintype "passive"))
    )
    (net (code "77") (name "/JTMS") (class "Default")
      (node (ref "P3") (pin "3") (pinfunction "3_3") (pintype "passive"))
      (node (ref "U1") (pin "34") (pinfunction "PA13/JTMS/SWDIO_34") (pintype "passive"))
    )
    (net (code "78") (name "/LED1") (class "Default")
      (node (ref "R2") (pin "1") (pintype "passive"))
      (node (ref "U1") (pin "2") (pinfunction "PC13-TAMPER-RTC_2") (pintype "passive"))
    )
    (net (code "79") (name "/NRST") (class "Default")
      (node (ref "C10") (pin "1") (pintype "passive"))
      (node (ref "R6") (pin "1") (pintype "passive"))
      (node (ref "RESET") (pin "1") (pinfunction "1_1") (pintype "passive"))
      (node (ref "U1") (pin "7") (pinfunction "NRST_7") (pintype "passive"))
    )
    (net (code "80") (name "/OPEN_0") (class "Default")
      (node (ref "G1") (pin "5") (pinfunction "14_5") (pintype "passive"))
      (node (ref "G1") (pin "8") (pinfunction "14_8") (pintype "passive"))
      (node (ref "P6") (pin "1") (pinfunction "1_1") (pintype "passive"))
    )
    (net (code "81") (name "/OPEN_1") (class "Default")
      (node (ref "G3") (pin "5") (pinfunction "14_5") (pintype "passive"))
      (node (ref "G3") (pin "8") (pinfunction "14_8") (pintype "passive"))
      (node (ref "P9") (pin "1") (pinfunction "1_1") (pintype "passive"))
    )
    (net (code "82") (name "/OPEN_2") (class "Default")
      (node (ref "G5") (pin "5") (pinfunction "14_5") (pintype "passive"))
      (node (ref "G5") (pin "8") (pinfunction "14_8") (pintype "passive"))
      (node (ref "P13") (pin "1") (pinfunction "1_1") (pintype "passive"))
    )
    (net (code "83") (name "/OPEN_3") (class "Default")
      (node (ref "G7") (pin "5") (pinfunction "14_5") (pintype "passive"))
      (node (ref "G7") (pin "8") (pinfunction "14_8") (pintype "passive"))
      (node (ref "P16") (pin "1") (pinfunction "1_1") (pintype "passive"))
    )
    (net (code "84") (name "/OPEN_4") (class "Default")
      (node (ref "G9") (pin "5") (pinfunction "14_5") (pintype "passive"))
      (node (ref "G9") (pin "8") (pinfunction "14_8") (pintype "passive"))
      (node (ref "P20") (pin "1") (pinfunction "1_1") (pintype "passive"))
    )
    (net (code "85") (name "/OPEN_5") (class "Default")
      (node (ref "G2") (pin "5") (pinfunction "14_5") (pintype "passive"))
      (node (ref "G2") (pin "8") (pinfunction "14_8") (pintype "passive"))
      (node (ref "P7") (pin "1") (pinfunction "1_1") (pintype "passive"))
    )
    (net (code "86") (name "/OPEN_6") (class "Default")
      (node (ref "G4") (pin "5") (pinfunction "14_5") (pintype "passive"))
      (node (ref "G4") (pin "8") (pinfunction "14_8") (pintype "passive"))
      (node (ref "P10") (pin "1") (pinfunction "1_1") (pintype "passive"))
    )
    (net (code "87") (name "/OPEN_7") (class "Default")
      (node (ref "G6") (pin "5") (pinfunction "14_5") (pintype "passive"))
      (node (ref "G6") (pin "8") (pinfunction "14_8") (pintype "passive"))
      (node (ref "P14") (pin "1") (pinfunction "1_1") (pintype "passive"))
    )
    (net (code "88") (name "/OPEN_8") (class "Default")
      (node (ref "G8") (pin "5") (pinfunction "14_5") (pintype "passive"))
      (node (ref "G8") (pin "8") (pinfunction "14_8") (pintype "passive"))
      (node (ref "P17") (pin "1") (pinfunction "1_1") (pintype "passive"))
    )
    (net (code "89") (name "/OPEN_9") (class "Default")
      (node (ref "G10") (pin "5") (pinfunction "14_5") (pintype "passive"))
      (node (ref "G10") (pin "8") (pinfunction "14_8") (pintype "passive"))
      (node (ref "P21") (pin "1") (pinfunction "1_1") (pintype "passive"))
    )
    (net (code "90") (name "/OPEN_10") (class "Default")
      (node (ref "G12") (pin "5") (pinfunction "14_5") (pintype "passive"))
      (node (ref "G12") (pin "8") (pinfunction "14_8") (pintype "passive"))
      (node (ref "P26") (pin "1") (pinfunction "1_1") (pintype "passive"))
    )
    (net (code "91") (name "/OPEN_11") (class "Default")
      (node (ref "G11") (pin "5") (pinfunction "14_5") (pintype "passive"))
      (node (ref "G11") (pin "8") (pinfunction "14_8") (pintype "passive"))
      (node (ref "P25") (pin "1") (pinfunction "1_1") (pintype "passive"))
    )
    (net (code "92") (name "/U1_RX") (class "Default")
      (node (ref "P24") (pin "4") (pinfunction "4_4") (pintype "passive"))
      (node (ref "U1") (pin "31") (pinfunction "PA10/USART1_RX/TIM1_CH3_31") (pintype "passive"))
    )
    (net (code "93") (name "/U1_TX") (class "Default")
      (node (ref "P24") (pin "5") (pinfunction "5_5") (pintype "passive"))
      (node (ref "U1") (pin "30") (pinfunction "PA9/USART1_TX/TIM1_CH2_30") (pintype "passive"))
    )
    (net (code "94") (name "/U2_RX") (class "Default")
      (node (ref "P1") (pin "2") (pinfunction "2_2") (pintype "passive"))
      (node (ref "U1") (pin "13") (pinfunction "PA3/USART2_RX/ADC12_IN3/TIM2CH4_13") (pintype "passive"))
    )
    (net (code "95") (name "/U2_TX") (class "Default")
      (node (ref "P1") (pin "1") (pinfunction "1_1") (pintype "passive"))
      (node (ref "U1") (pin "12") (pinfunction "PA2/USART2_TX/ADC12_IN2/TIM2CH3_12") (pintype "passive"))
    )
    (net (code "96") (name "GND") (class "Default")
      (node (ref "C1") (pin "2") (pinfunction "2_2") (pintype "passive"))
      (node (ref "C10") (pin "2") (pintype "passive"))
      (node (ref "C2") (pin "2") (pinfunction "2_2") (pintype "passive"))
      (node (ref "C3") (pin "2") (pinfunction "2_2") (pintype "passive"))
      (node (ref "C4") (pin "2") (pinfunction "2_2") (pintype "passive"))
      (node (ref "C5") (pin "2") (pinfunction "GND_2") (pintype "passive"))
      (node (ref "C6") (pin "2") (pinfunction "2_2") (pintype "passive"))
      (node (ref "C7") (pin "1") (pintype "passive"))
      (node (ref "C8") (pin "2") (pintype "passive"))
      (node (ref "C9") (pin "2") (pinfunction "2_2") (pintype "passive"))
      (node (ref "D1") (pin "K") (pinfunction "K_K") (pintype "passive"))
      (node (ref "D11") (pin "1") (pinfunction "A_1") (pintype "passive"))
      (node (ref "D12") (pin "1") (pinfunction "A_1") (pintype "passive"))
      (node (ref "D15") (pin "1") (pinfunction "A_1") (pintype "passive"))
      (node (ref "D16") (pin "1") (pinfunction "A_1") (pintype "passive"))
      (node (ref "D18") (pin "1") (pinfunction "A_1") (pintype "passive"))
      (node (ref "D19") (pin "1") (pinfunction "A_1") (pintype "passive"))
      (node (ref "D35") (pin "1") (pinfunction "A_1") (pintype "passive"))
      (node (ref "D36") (pin "1") (pinfunction "A_1") (pintype "passive"))
      (node (ref "D4") (pin "1") (pinfunction "A_1") (pintype "passive"))
      (node (ref "D5") (pin "1") (pinfunction "A_1") (pintype "passive"))
      (node (ref "D8") (pin "1") (pinfunction "A_1") (pintype "passive"))
      (node (ref "D9") (pin "1") (pinfunction "A_1") (pintype "passive"))
      (node (ref "G1") (pin "1") (pinfunction "17_1") (pintype "passive"))
      (node (ref "G10") (pin "1") (pinfunction "17_1") (pintype "passive"))
      (node (ref "G11") (pin "1") (pinfunction "17_1") (pintype "passive"))
      (node (ref "G12") (pin "1") (pinfunction "17_1") (pintype "passive"))
      (node (ref "G2") (pin "1") (pinfunction "17_1") (pintype "passive"))
      (node (ref "G3") (pin "1") (pinfunction "17_1") (pintype "passive"))
      (node (ref "G4") (pin "1") (pinfunction "17_1") (pintype "passive"))
      (node (ref "G5") (pin "1") (pinfunction "17_1") (pintype "passive"))
      (node (ref "G6") (pin "1") (pinfunction "17_1") (pintype "passive"))
      (node (ref "G7") (pin "1") (pinfunction "17_1") (pintype "passive"))
      (node (ref "G8") (pin "1") (pinfunction "17_1") (pintype "passive"))
      (node (ref "G9") (pin "1") (pinfunction "17_1") (pintype "passive"))
      (node (ref "J1") (pin "1") (pinfunction "-VIN_1") (pintype "passive"))
      (node (ref "J1") (pin "5") (pinfunction "GND_5") (pintype "passive"))
      (node (ref "P1") (pin "3") (pinfunction "3_3") (pintype "passive"))
      (node (ref "P11") (pin "1") (pinfunction "1_1") (pintype "passive"))
      (node (ref "P12") (pin "1") (pinfunction "1_1") (pintype "passive"))
      (node (ref "P15") (pin "1") (pinfunction "1_1") (pintype "passive"))
      (node (ref "P18") (pin "1") (pinfunction "1_1") (pintype "passive"))
      (node (ref "P19") (pin "1") (pinfunction "1_1") (pintype "passive"))
      (node (ref "P2") (pin "2") (pinfunction "2_2") (pintype "passive"))
      (node (ref "P22") (pin "1") (pinfunction "1_1") (pintype "passive"))
      (node (ref "P23") (pin "1") (pinfunction "1_1") (pintype "passive"))
      (node (ref "P24") (pin "1") (pinfunction "1_1") (pintype "passive"))
      (node (ref "P24") (pin "6") (pinfunction "6_6") (pintype "passive"))
      (node (ref "P24") (pin "7") (pinfunction "7_7") (pintype "passive"))
      (node (ref "P27") (pin "1") (pinfunction "1_1") (pintype "passive"))
      (node (ref "P3") (pin "2") (pinfunction "2_2") (pintype "passive"))
      (node (ref "P4") (pin "1") (pinfunction "1_1") (pintype "passive"))
      (node (ref "P5") (pin "1") (pinfunction "1_1") (pintype "passive"))
      (node (ref "P8") (pin "1") (pinfunction "1_1") (pintype "passive"))
      (node (ref "RESET") (pin "2") (pinfunction "2_2") (pintype "passive"))
      (node (ref "U1") (pin "20") (pinfunction "PB2/BOOT1_20") (pintype "passive"))
      (node (ref "U1") (pin "23") (pinfunction "VSS_1_23") (pintype "passive"))
      (node (ref "U1") (pin "35") (pinfunction "VSS_2_35") (pintype "passive"))
      (node (ref "U1") (pin "44") (pinfunction "BOOT0_44") (pintype "passive"))
      (node (ref "U1") (pin "47") (pinfunction "VSS_3_47") (pintype "passive"))
      (node (ref "U1") (pin "8") (pinfunction "VSSA_8") (pintype "passive"))
      (node (ref "U12") (pin "3") (pintype "passive"))
      (node (ref "U14") (pin "3") (pintype "passive"))
      (node (ref "U17") (pin "3") (pintype "passive"))
      (node (ref "U2") (pin "1") (pinfunction "GND_1") (pintype "passive"))
      (node (ref "U20") (pin "3") (pintype "passive"))
      (node (ref "U21") (pin "3") (pintype "passive"))
      (node (ref "U22") (pin "3") (pintype "passive"))
      (node (ref "U23") (pin "3") (pintype "passive"))
      (node (ref "U26") (pin "3") (pintype "passive"))
      (node (ref "U3") (pin "2") (pinfunction "GND_2") (pintype "power_in"))
      (node (ref "U3") (pin "8") (pinfunction "RS_8") (pintype "input"))
      (node (ref "U4") (pin "3") (pintype "passive"))
      (node (ref "U7") (pin "3") (pintype "passive"))
      (node (ref "U9") (pin "3") (pintype "passive"))
    )
    (net (code "97") (name "Net-(D1-PadA)") (class "Default")
      (node (ref "D1") (pin "A") (pinfunction "A_A") (pintype "passive"))
      (node (ref "R1") (pin "2") (pintype "passive"))
    )
    (net (code "98") (name "Net-(D2-PadK)") (class "Default")
      (node (ref "D2") (pin "K") (pinfunction "K_K") (pintype "passive"))
      (node (ref "R2") (pin "2") (pintype "passive"))
    )
    (net (code "99") (name "Net-(D3-PadA)") (class "Default")
      (node (ref "D3") (pin "A") (pinfunction "A_A") (pintype "passive"))
      (node (ref "U4") (pin "2") (pintype "passive"))
    )
    (net (code "100") (name "Net-(D6-PadA)") (class "Default")
      (node (ref "D6") (pin "A") (pinfunction "A_A") (pintype "passive"))
      (node (ref "U7") (pin "2") (pintype "passive"))
    )
    (net (code "101") (name "Net-(D7-PadA)") (class "Default")
      (node (ref "D7") (pin "A") (pinfunction "A_A") (pintype "passive"))
      (node (ref "U9") (pin "2") (pintype "passive"))
    )
    (net (code "102") (name "Net-(D10-PadA)") (class "Default")
      (node (ref "D10") (pin "A") (pinfunction "A_A") (pintype "passive"))
      (node (ref "U12") (pin "2") (pintype "passive"))
    )
    (net (code "103") (name "Net-(D13-PadA)") (class "Default")
      (node (ref "D13") (pin "A") (pinfunction "A_A") (pintype "passive"))
      (node (ref "U14") (pin "2") (pintype "passive"))
    )
    (net (code "104") (name "Net-(D14-PadA)") (class "Default")
      (node (ref "D14") (pin "A") (pinfunction "A_A") (pintype "passive"))
      (node (ref "U17") (pin "2") (pintype "passive"))
    )
    (net (code "105") (name "Net-(D17-PadA)") (class "Default")
      (node (ref "D17") (pin "A") (pinfunction "A_A") (pintype "passive"))
      (node (ref "U20") (pin "2") (pintype "passive"))
    )
    (net (code "106") (name "Net-(D20-PadA)") (class "Default")
      (node (ref "D20") (pin "A") (pinfunction "A_A") (pintype "passive"))
      (node (ref "U21") (pin "2") (pintype "passive"))
    )
    (net (code "107") (name "Net-(D21-PadA)") (class "Default")
      (node (ref "D21") (pin "A") (pinfunction "A_A") (pintype "passive"))
      (node (ref "U22") (pin "2") (pintype "passive"))
    )
    (net (code "108") (name "Net-(D22-PadA)") (class "Default")
      (node (ref "D22") (pin "A") (pinfunction "A_A") (pintype "passive"))
      (node (ref "U23") (pin "2") (pintype "passive"))
    )
    (net (code "109") (name "Net-(D23-PadA)") (class "Default")
      (node (ref "D23") (pin "A") (pinfunction "A_A") (pintype "passive"))
      (node (ref "R4") (pin "2") (pintype "passive"))
    )
    (net (code "110") (name "Net-(D24-PadA)") (class "Default")
      (node (ref "D24") (pin "A") (pinfunction "A_A") (pintype "passive"))
      (node (ref "U5") (pin "3") (pintype "passive"))
    )
    (net (code "111") (name "Net-(D25-PadA)") (class "Default")
      (node (ref "D25") (pin "A") (pinfunction "A_A") (pintype "passive"))
      (node (ref "U6") (pin "3") (pintype "passive"))
    )
    (net (code "112") (name "Net-(D26-PadA)") (class "Default")
      (node (ref "D26") (pin "A") (pinfunction "A_A") (pintype "passive"))
      (node (ref "U8") (pin "3") (pintype "passive"))
    )
    (net (code "113") (name "Net-(D27-PadA)") (class "Default")
      (node (ref "D27") (pin "A") (pinfunction "A_A") (pintype "passive"))
      (node (ref "U10") (pin "3") (pintype "passive"))
    )
    (net (code "114") (name "Net-(D28-PadA)") (class "Default")
      (node (ref "D28") (pin "A") (pinfunction "A_A") (pintype "passive"))
      (node (ref "U11") (pin "3") (pintype "passive"))
    )
    (net (code "115") (name "Net-(D29-PadA)") (class "Default")
      (node (ref "D29") (pin "A") (pinfunction "A_A") (pintype "passive"))
      (node (ref "U13") (pin "3") (pintype "passive"))
    )
    (net (code "116") (name "Net-(D30-PadA)") (class "Default")
      (node (ref "D30") (pin "A") (pinfunction "A_A") (pintype "passive"))
      (node (ref "U15") (pin "3") (pintype "passive"))
    )
    (net (code "117") (name "Net-(D31-PadA)") (class "Default")
      (node (ref "D31") (pin "A") (pinfunction "A_A") (pintype "passive"))
      (node (ref "U16") (pin "3") (pintype "passive"))
    )
    (net (code "118") (name "Net-(D32-PadA)") (class "Default")
      (node (ref "D32") (pin "A") (pinfunction "A_A") (pintype "passive"))
      (node (ref "U18") (pin "3") (pintype "passive"))
    )
    (net (code "119") (name "Net-(D33-PadA)") (class "Default")
      (node (ref "D33") (pin "A") (pinfunction "A_A") (pintype "passive"))
      (node (ref "U19") (pin "3") (pintype "passive"))
    )
    (net (code "120") (name "Net-(D34-PadA)") (class "Default")
      (node (ref "D34") (pin "A") (pinfunction "A_A") (pintype "passive"))
      (node (ref "U24") (pin "3") (pintype "passive"))
    )
    (net (code "121") (name "Net-(D37-PadA)") (class "Default")
      (node (ref "D37") (pin "A") (pinfunction "A_A") (pintype "passive"))
      (node (ref "U25") (pin "3") (pintype "passive"))
    )
    (net (code "122") (name "Net-(D38-PadA)") (class "Default")
      (node (ref "D38") (pin "A") (pinfunction "A_A") (pintype "passive"))
      (node (ref "U26") (pin "2") (pintype "passive"))
    )
    (net (code "123") (name "Net-(K1-TAP1)") (class "Default")
      (node (ref "K1") (pin "2") (pinfunction "TAP1_2") (pintype "passive"))
      (node (ref "U2") (pin "3") (pinfunction "IN_3") (pintype "passive"))
    )
    (net (code "124") (name "Net-(R5-Pad2)") (class "Default")
      (node (ref "R5") (pin "2") (pintype "passive"))
      (node (ref "U24") (pin "2") (pintype "passive"))
    )
    (net (code "125") (name "Net-(R7-Pad1)") (class "Default")
      (node (ref "R7") (pin "1") (pintype "passive"))
      (node (ref "U4") (pin "1") (pintype "passive"))
    )
    (net (code "126") (name "Net-(R9-Pad2)") (class "Default")
      (node (ref "R9") (pin "2") (pintype "passive"))
      (node (ref "U5") (pin "2") (pintype "passive"))
    )
    (net (code "127") (name "Net-(R10-Pad1)") (class "Default")
      (node (ref "R10") (pin "1") (pintype "passive"))
      (node (ref "U7") (pin "1") (pintype "passive"))
    )
    (net (code "128") (name "Net-(R11-Pad2)") (class "Default")
      (node (ref "R11") (pin "2") (pintype "passive"))
      (node (ref "U6") (pin "2") (pintype "passive"))
    )
    (net (code "129") (name "Net-(R13-Pad2)") (class "Default")
      (node (ref "R13") (pin "2") (pintype "passive"))
      (node (ref "U8") (pin "2") (pintype "passive"))
    )
    (net (code "130") (name "Net-(R14-Pad1)") (class "Default")
      (node (ref "R14") (pin "1") (pintype "passive"))
      (node (ref "U9") (pin "1") (pintype "passive"))
    )
    (net (code "131") (name "Net-(R16-Pad2)") (class "Default")
      (node (ref "R16") (pin "2") (pintype "passive"))
      (node (ref "U10") (pin "2") (pintype "passive"))
    )
    (net (code "132") (name "Net-(R17-Pad1)") (class "Default")
      (node (ref "R17") (pin "1") (pintype "passive"))
      (node (ref "U12") (pin "1") (pintype "passive"))
    )
    (net (code "133") (name "Net-(R19-Pad2)") (class "Default")
      (node (ref "R19") (pin "2") (pintype "passive"))
      (node (ref "U11") (pin "2") (pintype "passive"))
    )
    (net (code "134") (name "Net-(R20-Pad2)") (class "Default")
      (node (ref "R20") (pin "2") (pintype "passive"))
      (node (ref "U13") (pin "2") (pintype "passive"))
    )
    (net (code "135") (name "Net-(R21-Pad1)") (class "Default")
      (node (ref "R21") (pin "1") (pintype "passive"))
      (node (ref "U14") (pin "1") (pintype "passive"))
    )
    (net (code "136") (name "Net-(R23-Pad2)") (class "Default")
      (node (ref "R23") (pin "2") (pintype "passive"))
      (node (ref "U15") (pin "2") (pintype "passive"))
    )
    (net (code "137") (name "Net-(R24-Pad1)") (class "Default")
      (node (ref "R24") (pin "1") (pintype "passive"))
      (node (ref "U17") (pin "1") (pintype "passive"))
    )
    (net (code "138") (name "Net-(R25-Pad2)") (class "Default")
      (node (ref "R25") (pin "2") (pintype "passive"))
      (node (ref "U16") (pin "2") (pintype "passive"))
    )
    (net (code "139") (name "Net-(R27-Pad2)") (class "Default")
      (node (ref "R27") (pin "2") (pintype "passive"))
      (node (ref "U18") (pin "2") (pintype "passive"))
    )
    (net (code "140") (name "Net-(R28-Pad1)") (class "Default")
      (node (ref "R28") (pin "1") (pintype "passive"))
      (node (ref "U20") (pin "1") (pintype "passive"))
    )
    (net (code "141") (name "Net-(R29-Pad2)") (class "Default")
      (node (ref "R29") (pin "2") (pintype "passive"))
      (node (ref "U19") (pin "2") (pintype "passive"))
    )
    (net (code "142") (name "Net-(R31-Pad1)") (class "Default")
      (node (ref "R31") (pin "1") (pintype "passive"))
      (node (ref "U21") (pin "1") (pintype "passive"))
    )
    (net (code "143") (name "Net-(R33-Pad1)") (class "Default")
      (node (ref "R33") (pin "1") (pintype "passive"))
      (node (ref "U22") (pin "1") (pintype "passive"))
    )
    (net (code "144") (name "Net-(R35-Pad1)") (class "Default")
      (node (ref "R35") (pin "1") (pintype "passive"))
      (node (ref "U23") (pin "1") (pintype "passive"))
    )
    (net (code "145") (name "Net-(R37-Pad2)") (class "Default")
      (node (ref "R37") (pin "2") (pintype "passive"))
      (node (ref "U25") (pin "2") (pintype "passive"))
    )
    (net (code "146") (name "Net-(R38-Pad1)") (class "Default")
      (node (ref "R38") (pin "1") (pintype "passive"))
      (node (ref "U26") (pin "1") (pintype "passive"))
    )
    (net (code "147") (name "Net-(U1-PD0-OSC_IN)") (class "Default")
      (node (ref "C6") (pin "1") (pinfunction "1_1") (pintype "passive"))
      (node (ref "U1") (pin "5") (pinfunction "PD0-OSC_IN_5") (pintype "passive"))
      (node (ref "Y1") (pin "1") (pinfunction "OSC1_1") (pintype "passive"))
    )
    (net (code "148") (name "Net-(U1-PD1-OSC_OUT{slash}CANTX)") (class "Default")
      (node (ref "C9") (pin "1") (pinfunction "1_1") (pintype "passive"))
      (node (ref "U1") (pin "6") (pinfunction "PD1-OSC_OUT/CANTX_6") (pintype "passive"))
      (node (ref "Y1") (pin "2") (pinfunction "OSC2_2") (pintype "passive"))
    )
    (net (code "149") (name "VCC") (class "Default")
      (node (ref "J1") (pin "3") (pinfunction "+V0_3") (pintype "passive"))
      (node (ref "K1") (pin "3") (pinfunction "I/O1_3") (pintype "passive"))
    )
    (net (code "150") (name "VCC3.3") (class "Default")
      (node (ref "C1") (pin "1") (pinfunction "1_1") (pintype "passive"))
      (node (ref "C2") (pin "1") (pinfunction "1_1") (pintype "passive"))
      (node (ref "C3") (pin "1") (pinfunction "1_1") (pintype "passive"))
      (node (ref "C4") (pin "1") (pinfunction "1_1") (pintype "passive"))
      (node (ref "C5") (pin "1") (pinfunction "VCC_1") (pintype "passive"))
      (node (ref "C7") (pin "2") (pintype "passive"))
      (node (ref "C8") (pin "1") (pintype "passive"))
      (node (ref "D2") (pin "A") (pinfunction "A_A") (pintype "passive"))
      (node (ref "P1") (pin "4") (pinfunction "4_4") (pintype "passive"))
      (node (ref "P24") (pin "2") (pinfunction "2_2") (pintype "passive"))
      (node (ref "P3") (pin "1") (pinfunction "1_1") (pintype "passive"))
      (node (ref "R1") (pin "1") (pintype "passive"))
      (node (ref "R12") (pin "2") (pintype "passive"))
      (node (ref "R15") (pin "2") (pintype "passive"))
      (node (ref "R18") (pin "2") (pintype "passive"))
      (node (ref "R22") (pin "2") (pintype "passive"))
      (node (ref "R26") (pin "2") (pintype "passive"))
      (node (ref "R30") (pin "2") (pintype "passive"))
      (node (ref "R32") (pin "2") (pintype "passive"))
      (node (ref "R34") (pin "2") (pintype "passive"))
      (node (ref "R36") (pin "2") (pintype "passive"))
      (node (ref "R39") (pin "2") (pintype "passive"))
      (node (ref "R4") (pin "1") (pintype "passive"))
      (node (ref "R6") (pin "2") (pintype "passive"))
      (node (ref "R8") (pin "2") (pintype "passive"))
      (node (ref "U1") (pin "1") (pinfunction "VBAT_1") (pintype "passive"))
      (node (ref "U1") (pin "24") (pinfunction "VDD_1_24") (pintype "passive"))
      (node (ref "U1") (pin "36") (pinfunction "VDD_2_36") (pintype "passive"))
      (node (ref "U1") (pin "48") (pinfunction "VDD_3_48") (pintype "passive"))
      (node (ref "U1") (pin "9") (pinfunction "VDDA_9") (pintype "passive"))
      (node (ref "U10") (pin "1") (pintype "passive"))
      (node (ref "U11") (pin "1") (pintype "passive"))
      (node (ref "U13") (pin "1") (pintype "passive"))
      (node (ref "U15") (pin "1") (pintype "passive"))
      (node (ref "U16") (pin "1") (pintype "passive"))
      (node (ref "U18") (pin "1") (pintype "passive"))
      (node (ref "U19") (pin "1") (pintype "passive"))
      (node (ref "U2") (pin "2") (pinfunction "OUT_2") (pintype "passive"))
      (node (ref "U2") (pin "4") (pinfunction "OUT_4") (pintype "passive"))
      (node (ref "U24") (pin "1") (pintype "passive"))
      (node (ref "U25") (pin "1") (pintype "passive"))
      (node (ref "U3") (pin "3") (pinfunction "VCC_3") (pintype "power_in"))
      (node (ref "U5") (pin "1") (pintype "passive"))
      (node (ref "U6") (pin "1") (pintype "passive"))
      (node (ref "U8") (pin "1") (pintype "passive"))
    )
    (net (code "151") (name "VCC24") (class "Default")
      (node (ref "J1") (pin "2") (pinfunction "+VIN_2") (pintype "passive"))
      (node (ref "P11") (pin "3") (pinfunction "3_3") (pintype "passive"))
      (node (ref "P12") (pin "3") (pinfunction "3_3") (pintype "passive"))
      (node (ref "P15") (pin "3") (pinfunction "3_3") (pintype "passive"))
      (node (ref "P18") (pin "3") (pinfunction "3_3") (pintype "passive"))
      (node (ref "P19") (pin "3") (pinfunction "3_3") (pintype "passive"))
      (node (ref "P2") (pin "1") (pinfunction "1_1") (pintype "passive"))
      (node (ref "P22") (pin "3") (pinfunction "3_3") (pintype "passive"))
      (node (ref "P23") (pin "3") (pinfunction "3_3") (pintype "passive"))
      (node (ref "P27") (pin "3") (pinfunction "3_3") (pintype "passive"))
      (node (ref "P4") (pin "3") (pinfunction "3_3") (pintype "passive"))
      (node (ref "P5") (pin "3") (pinfunction "3_3") (pintype "passive"))
      (node (ref "P8") (pin "3") (pinfunction "3_3") (pintype "passive"))
      (node (ref "R10") (pin "2") (pintype "passive"))
      (node (ref "R14") (pin "2") (pintype "passive"))
      (node (ref "R17") (pin "2") (pintype "passive"))
      (node (ref "R21") (pin "2") (pintype "passive"))
      (node (ref "R24") (pin "2") (pintype "passive"))
      (node (ref "R28") (pin "2") (pintype "passive"))
      (node (ref "R31") (pin "2") (pintype "passive"))
      (node (ref "R33") (pin "2") (pintype "passive"))
      (node (ref "R35") (pin "2") (pintype "passive"))
      (node (ref "R38") (pin "2") (pintype "passive"))
      (node (ref "R7") (pin "2") (pintype "passive"))
      (node (ref "U10") (pin "4") (pintype "passive"))
      (node (ref "U11") (pin "4") (pintype "passive"))
      (node (ref "U13") (pin "4") (pintype "passive"))
      (node (ref "U15") (pin "4") (pintype "passive"))
      (node (ref "U16") (pin "4") (pintype "passive"))
      (node (ref "U18") (pin "4") (pintype "passive"))
      (node (ref "U19") (pin "4") (pintype "passive"))
      (node (ref "U24") (pin "4") (pintype "passive"))
      (node (ref "U25") (pin "4") (pintype "passive"))
      (node (ref "U5") (pin "4") (pintype "passive"))
      (node (ref "U6") (pin "4") (pintype "passive"))
      (node (ref "U8") (pin "4") (pintype "passive"))
    )
    (net (code "152") (name "unconnected-(J1-NC-Pad4)") (class "Default")
      (node (ref "J1") (pin "4") (pinfunction "NC_4") (pintype "passive"))
    )
    (net (code "153") (name "unconnected-(K1-I{slash}O1-Pad1)") (class "Default")
      (node (ref "K1") (pin "1") (pinfunction "I/O1_1") (pintype "passive"))
    )
    (net (code "154") (name "unconnected-(K1-I{slash}O2-Pad4)") (class "Default")
      (node (ref "K1") (pin "4") (pinfunction "I/O2_4") (pintype "passive"))
    )
    (net (code "155") (name "unconnected-(K1-I{slash}O2-Pad6)") (class "Default")
      (node (ref "K1") (pin "6") (pinfunction "I/O2_6") (pintype "passive"))
    )
    (net (code "156") (name "unconnected-(K1-TAP2-Pad5)") (class "Default")
      (node (ref "K1") (pin "5") (pinfunction "TAP2_5") (pintype "passive"))
    )
    (net (code "157") (name "unconnected-(U1-PC14-OSC32_IN-Pad3)") (class "Default")
      (node (ref "U1") (pin "3") (pinfunction "PC14-OSC32_IN_3") (pintype "passive"))
    )
    (net (code "158") (name "unconnected-(U1-PC15-OSC32_OUT-Pad4)") (class "Default")
      (node (ref "U1") (pin "4") (pinfunction "PC15-OSC32_OUT_4") (pintype "passive"))
    )
    (net (code "159") (name "unconnected-(U3-Vref-Pad5)") (class "Default")
      (node (ref "U3") (pin "5") (pinfunction "Vref_5") (pintype "output"))
    )
  )
)
